# FYP_DevBoard.net
KiCad netlist of a schematic drawn in EasyEDA
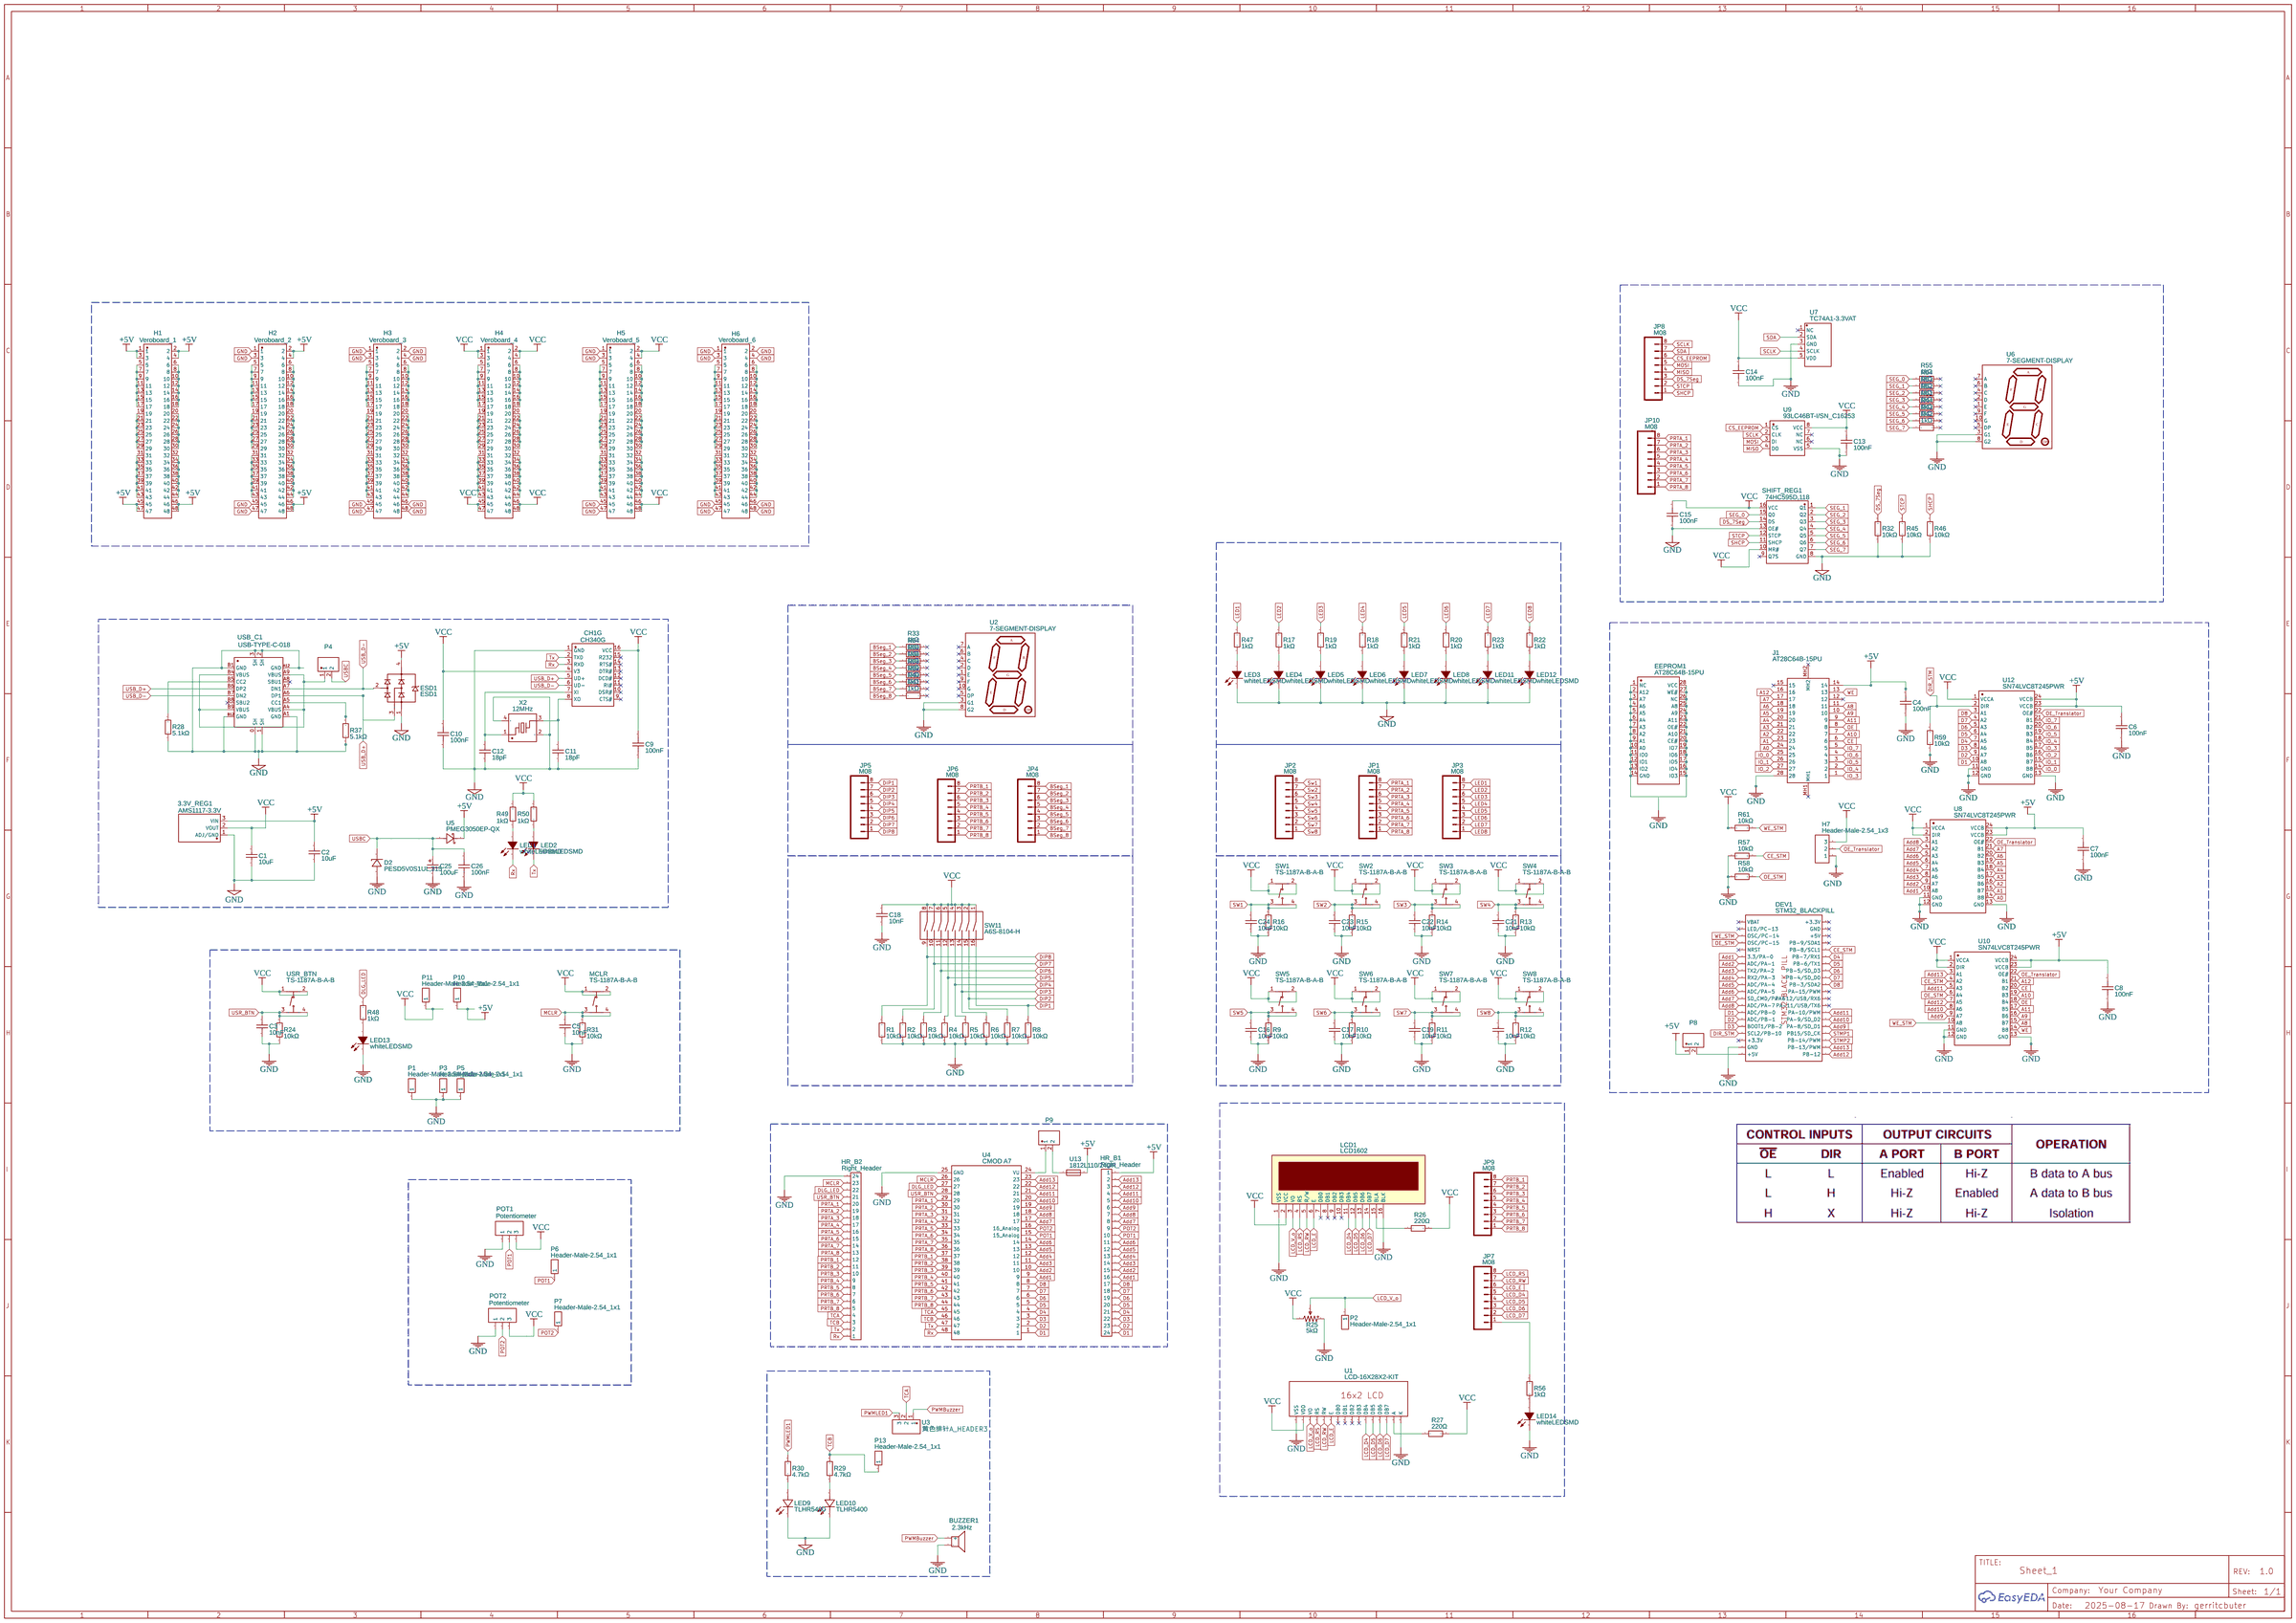
[diagram p0: schematic sheet]

(export (version "E")
  (design (tool "Eeschema 10.0.6"))
  (components
    (comp (ref "3.3V_REG1")
      (value "AMS1117-3.3V")
      (fields (field (name "Manufacturer") "MSKSEMI(美森科)"))
      (libsource (lib "") (part "AMS1117-3.3V_C5120796"))
    )
    (comp (ref "BUZZER1")
      (value "2.3kHz")
      (fields (field (name "Manufacturer") "华能"))
      (libsource (lib "") (part "TMB12A05"))
    )
    (comp (ref "C1")
      (value "10uF")
      (fields (field (name "Manufacturer") "SAMSUNG(三星)"))
      (libsource (lib "") (part "CL10A105KB8NNNC"))
    )
    (comp (ref "C2")
      (value "10uF")
      (fields (field (name "Manufacturer") "SAMSUNG(三星)"))
      (libsource (lib "") (part "CL10A105KB8NNNC"))
    )
    (comp (ref "C3")
      (value "10nF")
      (fields (field (name "Manufacturer Part") "0603B103K500NT") (field (name "Manufacturer") "FH(风华)"))
      (libsource (lib "") (part "0603B103K500NT"))
    )
    (comp (ref "C4")
      (value "100nF")
      (fields
        (field (name "Manufacturer Part") "CC0603KRX7R9BB104")
        (field (name "Manufacturer") "YAGEO(国巨)")
      )
      (libsource (lib "") (part "CC0603KRX7R9BB104"))
    )
    (comp (ref "C5")
      (value "10nF")
      (fields (field (name "Manufacturer Part") "0603B103K500NT") (field (name "Manufacturer") "FH(风华)"))
      (libsource (lib "") (part "0603B103K500NT"))
    )
    (comp (ref "C6")
      (value "100nF")
      (fields
        (field (name "Manufacturer Part") "CC0603KRX7R9BB104")
        (field (name "Manufacturer") "YAGEO(国巨)")
      )
      (libsource (lib "") (part "CC0603KRX7R9BB104"))
    )
    (comp (ref "C7")
      (value "100nF")
      (fields
        (field (name "Manufacturer Part") "CC0603KRX7R9BB104")
        (field (name "Manufacturer") "YAGEO(国巨)")
      )
      (libsource (lib "") (part "CC0603KRX7R9BB104"))
    )
    (comp (ref "C8")
      (value "100nF")
      (fields
        (field (name "Manufacturer Part") "CC0603KRX7R9BB104")
        (field (name "Manufacturer") "YAGEO(国巨)")
      )
      (libsource (lib "") (part "CC0603KRX7R9BB104"))
    )
    (comp (ref "C9")
      (value "100nF")
      (fields
        (field (name "Manufacturer Part") "CC0603KRX7R9BB104")
        (field (name "Manufacturer") "YAGEO(国巨)")
      )
      (libsource (lib "") (part "CC0603KRX7R9BB104"))
    )
    (comp (ref "C10")
      (value "100nF")
      (fields
        (field (name "Manufacturer Part") "CC0603KRX7R9BB104")
        (field (name "Manufacturer") "YAGEO(国巨)")
      )
      (libsource (lib "") (part "CC0603KRX7R9BB104"))
    )
    (comp (ref "C11")
      (value "18pF")
      (fields
        (field (name "Manufacturer Part") "CL10C180JB8NNNC")
        (field (name "Manufacturer") "SAMSUNG(三星)")
      )
      (libsource (lib "") (part "CL10C180JB8NNNC"))
    )
    (comp (ref "C12")
      (value "18pF")
      (fields
        (field (name "Manufacturer Part") "CL10C180JB8NNNC")
        (field (name "Manufacturer") "SAMSUNG(三星)")
      )
      (libsource (lib "") (part "CL10C180JB8NNNC"))
    )
    (comp (ref "C13")
      (value "100nF")
      (fields
        (field (name "Manufacturer Part") "CC0603KRX7R9BB104")
        (field (name "Manufacturer") "YAGEO(国巨)")
      )
      (libsource (lib "") (part "CC0603KRX7R9BB104"))
    )
    (comp (ref "C14")
      (value "100nF")
      (fields
        (field (name "Manufacturer Part") "CC0603KRX7R9BB104")
        (field (name "Manufacturer") "YAGEO(国巨)")
      )
      (libsource (lib "") (part "CC0603KRX7R9BB104"))
    )
    (comp (ref "C15")
      (value "100nF")
      (fields
        (field (name "Manufacturer Part") "CC0603KRX7R9BB104")
        (field (name "Manufacturer") "YAGEO(国巨)")
      )
      (libsource (lib "") (part "CC0603KRX7R9BB104"))
    )
    (comp (ref "C16")
      (value "10nF")
      (fields (field (name "Manufacturer Part") "0603B103K500NT") (field (name "Manufacturer") "FH(风华)"))
      (libsource (lib "") (part "0603B103K500NT"))
    )
    (comp (ref "C17")
      (value "10nF")
      (fields (field (name "Manufacturer Part") "0603B103K500NT") (field (name "Manufacturer") "FH(风华)"))
      (libsource (lib "") (part "0603B103K500NT"))
    )
    (comp (ref "C18")
      (value "10nF")
      (fields (field (name "Manufacturer Part") "0603B103K500NT") (field (name "Manufacturer") "FH(风华)"))
      (libsource (lib "") (part "0603B103K500NT"))
    )
    (comp (ref "C19")
      (value "10nF")
      (fields (field (name "Manufacturer Part") "0603B103K500NT") (field (name "Manufacturer") "FH(风华)"))
      (libsource (lib "") (part "0603B103K500NT"))
    )
    (comp (ref "C20")
      (value "10nF")
      (fields (field (name "Manufacturer Part") "0603B103K500NT") (field (name "Manufacturer") "FH(风华)"))
      (libsource (lib "") (part "0603B103K500NT"))
    )
    (comp (ref "C21")
      (value "10nF")
      (fields (field (name "Manufacturer Part") "0603B103K500NT") (field (name "Manufacturer") "FH(风华)"))
      (libsource (lib "") (part "0603B103K500NT"))
    )
    (comp (ref "C22")
      (value "10nF")
      (fields (field (name "Manufacturer Part") "0603B103K500NT") (field (name "Manufacturer") "FH(风华)"))
      (libsource (lib "") (part "0603B103K500NT"))
    )
    (comp (ref "C23")
      (value "10nF")
      (fields (field (name "Manufacturer Part") "0603B103K500NT") (field (name "Manufacturer") "FH(风华)"))
      (libsource (lib "") (part "0603B103K500NT"))
    )
    (comp (ref "C24")
      (value "10nF")
      (fields (field (name "Manufacturer Part") "0603B103K500NT") (field (name "Manufacturer") "FH(风华)"))
      (libsource (lib "") (part "0603B103K500NT"))
    )
    (comp (ref "C25")
      (value "100uF")
      (fields (field (name "Manufacturer Part") "TAJB107K006RNJ") (field (name "Manufacturer") "Kyocera AVX"))
      (libsource (lib "") (part "TAJB107K006RNJ"))
    )
    (comp (ref "C26")
      (value "100nF")
      (fields
        (field (name "Manufacturer Part") "CC0603KRX7R9BB104")
        (field (name "Manufacturer") "YAGEO(国巨)")
      )
      (libsource (lib "") (part "CC0603KRX7R9BB104"))
    )
    (comp (ref "CH1G")
      (value "CH340G")
      (fields (field (name "Manufacturer") "WCH(南京沁恒)"))
      (libsource (lib "") (part "CH340G"))
    )
    (comp (ref "D2")
      (value "PESD5V0S1UL,315")
      (fields (field (name "Manufacturer") "Nexperia(安世)"))
      (libsource (lib "") (part "PESD5V0S1UL,315"))
    )
    (comp (ref "DEV1") (value "STM32_BLACKPILL") (libsource (lib "") (part "STM32_BLACKPILL")))
    (comp (ref "EEPROM1")
      (value "AT28C64B-15PU")
      (fields (field (name "Manufacturer") "MICROCHIP(美国微芯)"))
      (libsource (lib "") (part "AT28C64B-15PU"))
    )
    (comp (ref "ESD1")
      (value "ESD1")
      (fields
        (field (name "Manufacturer Part") "TPPRTR5V0U2X")
        (field (name "Manufacturer") "TECH PUBLIC(台舟)")
      )
      (libsource (lib "") (part "TPPRTR5V0U2X"))
    )
    (comp (ref "H1")
      (value "Veroboard_1")
      (fields (field (name "Manufacturer") "XKB Connectivity(中国星坤)"))
      (libsource (lib "") (part "X5521FV-2X24-C70D30-1000"))
    )
    (comp (ref "H2")
      (value "Veroboard_2")
      (fields (field (name "Manufacturer") "XKB Connectivity(中国星坤)"))
      (libsource (lib "") (part "X5521FV-2X24-C70D30-1000"))
    )
    (comp (ref "H3")
      (value "Veroboard_3")
      (fields (field (name "Manufacturer") "XKB Connectivity(中国星坤)"))
      (libsource (lib "") (part "X5521FV-2X24-C70D30-1000"))
    )
    (comp (ref "H4")
      (value "Veroboard_4")
      (fields (field (name "Manufacturer") "XKB Connectivity(中国星坤)"))
      (libsource (lib "") (part "X5521FV-2X24-C70D30-1000"))
    )
    (comp (ref "H5")
      (value "Veroboard_5")
      (fields (field (name "Manufacturer") "XKB Connectivity(中国星坤)"))
      (libsource (lib "") (part "X5521FV-2X24-C70D30-1000"))
    )
    (comp (ref "H6")
      (value "Veroboard_6")
      (fields (field (name "Manufacturer") "XKB Connectivity(中国星坤)"))
      (libsource (lib "") (part "X5521FV-2X24-C70D30-1000"))
    )
    (comp (ref "H7")
      (value "Header-Male-2.54_1x3")
      (fields (field (name "Manufacturer Part") "2.54-1*3P针") (field (name "Manufacturer") "BOOMELE(博穆精密)"))
      (libsource (lib "") (part "Header-Male-2.54_1x3"))
    )
    (comp (ref "HR_B1") (value "Right_Header") (libsource (lib "") (part "Header_Female_2.54_1x24")))
    (comp (ref "HR_B2") (value "Right_Header") (libsource (lib "") (part "Header_Female_2.54_1x24_1")))
    (comp (ref "J1") (value "AT28C64B-15PU") (libsource (lib "") (part "28-6554-10")))
    (comp (ref "JP1") (value "M08") (libsource (lib "") (part "M08")))
    (comp (ref "JP2") (value "M08") (libsource (lib "") (part "M08")))
    (comp (ref "JP3") (value "M08") (libsource (lib "") (part "M08")))
    (comp (ref "JP4") (value "M08") (libsource (lib "") (part "M08")))
    (comp (ref "JP5") (value "M08") (libsource (lib "") (part "M08")))
    (comp (ref "JP6") (value "M08") (libsource (lib "") (part "M08")))
    (comp (ref "JP7") (value "M08") (libsource (lib "") (part "M08")))
    (comp (ref "JP8") (value "M08") (libsource (lib "") (part "M08")))
    (comp (ref "JP9") (value "M08") (libsource (lib "") (part "M08")))
    (comp (ref "JP10") (value "M08") (libsource (lib "") (part "M08")))
    (comp (ref "LCD1")
      (value "LCD1602")
      (fields
        (field (name "Manufacturer Part") "LCM1602K-NSW-BBW")
        (field (name "Manufacturer") "LONTECH(厦门龙特)")
      )
      (libsource (lib "") (part "LCD1602"))
    )
    (comp (ref "LED1")
      (value "whiteLEDSMD")
      (fields (field (name "Manufacturer Part") "KT-0805W") (field (name "Manufacturer") "KENTO"))
      (libsource (lib "") (part "whiteLEDSMD"))
    )
    (comp (ref "LED2")
      (value "whiteLEDSMD")
      (fields (field (name "Manufacturer Part") "KT-0805W") (field (name "Manufacturer") "KENTO"))
      (libsource (lib "") (part "whiteLEDSMD"))
    )
    (comp (ref "LED3")
      (value "whiteLEDSMD")
      (fields (field (name "Manufacturer Part") "KT-0805W") (field (name "Manufacturer") "KENTO"))
      (libsource (lib "") (part "whiteLEDSMD"))
    )
    (comp (ref "LED4")
      (value "whiteLEDSMD")
      (fields (field (name "Manufacturer Part") "KT-0805W") (field (name "Manufacturer") "KENTO"))
      (libsource (lib "") (part "whiteLEDSMD"))
    )
    (comp (ref "LED5")
      (value "whiteLEDSMD")
      (fields (field (name "Manufacturer Part") "KT-0805W") (field (name "Manufacturer") "KENTO"))
      (libsource (lib "") (part "whiteLEDSMD"))
    )
    (comp (ref "LED6")
      (value "whiteLEDSMD")
      (fields (field (name "Manufacturer Part") "KT-0805W") (field (name "Manufacturer") "KENTO"))
      (libsource (lib "") (part "whiteLEDSMD"))
    )
    (comp (ref "LED7")
      (value "whiteLEDSMD")
      (fields (field (name "Manufacturer Part") "KT-0805W") (field (name "Manufacturer") "KENTO"))
      (libsource (lib "") (part "whiteLEDSMD"))
    )
    (comp (ref "LED8")
      (value "whiteLEDSMD")
      (fields (field (name "Manufacturer Part") "KT-0805W") (field (name "Manufacturer") "KENTO"))
      (libsource (lib "") (part "whiteLEDSMD"))
    )
    (comp (ref "LED9")
      (value "TLHR5400")
      (fields (field (name "Manufacturer") "VISHAY(威世)"))
      (libsource (lib "") (part "TLHR5400"))
    )
    (comp (ref "LED10")
      (value "TLHR5400")
      (fields (field (name "Manufacturer") "VISHAY(威世)"))
      (libsource (lib "") (part "TLHR5400"))
    )
    (comp (ref "LED11")
      (value "whiteLEDSMD")
      (fields (field (name "Manufacturer Part") "KT-0805W") (field (name "Manufacturer") "KENTO"))
      (libsource (lib "") (part "whiteLEDSMD"))
    )
    (comp (ref "LED12")
      (value "whiteLEDSMD")
      (fields (field (name "Manufacturer Part") "KT-0805W") (field (name "Manufacturer") "KENTO"))
      (libsource (lib "") (part "whiteLEDSMD"))
    )
    (comp (ref "LED13")
      (value "whiteLEDSMD")
      (fields (field (name "Manufacturer Part") "KT-0805W") (field (name "Manufacturer") "KENTO"))
      (libsource (lib "") (part "whiteLEDSMD"))
    )
    (comp (ref "LED14")
      (value "whiteLEDSMD")
      (fields (field (name "Manufacturer Part") "KT-0805W") (field (name "Manufacturer") "KENTO"))
      (libsource (lib "") (part "whiteLEDSMD"))
    )
    (comp (ref "MCLR")
      (value "TS-1187A-B-A-B")
      (fields (field (name "Manufacturer") "XKB Connection(中国星坤)"))
      (libsource (lib "") (part "TS-1187A-B-A-B_1"))
    )
    (comp (ref "P1")
      (value "Header-Male-2.54_1x1")
      (fields (field (name "Manufacturer") "BOOMELE(博穆精密)"))
      (libsource (lib "") (part "Header-Male-2.54_1x1"))
    )
    (comp (ref "P2")
      (value "Header-Male-2.54_1x1")
      (fields (field (name "Manufacturer") "BOOMELE(博穆精密)"))
      (libsource (lib "") (part "Header-Male-2.54_1x1_1"))
    )
    (comp (ref "P3")
      (value "Header-Male-2.54_1x1")
      (fields (field (name "Manufacturer") "BOOMELE(博穆精密)"))
      (libsource (lib "") (part "Header-Male-2.54_1x1"))
    )
    (comp (ref "P4")
      (value "Female header1*2P")
      (fields (field (name "Manufacturer Part") "2.0-1*2P母") (field (name "Manufacturer") "BOOMELE(博穆精密)"))
      (libsource (lib "") (part "Female header1*2P"))
    )
    (comp (ref "P5")
      (value "Header-Male-2.54_1x1")
      (fields (field (name "Manufacturer") "BOOMELE(博穆精密)"))
      (libsource (lib "") (part "Header-Male-2.54_1x1"))
    )
    (comp (ref "P6")
      (value "Header-Male-2.54_1x1")
      (fields (field (name "Manufacturer") "BOOMELE(博穆精密)"))
      (libsource (lib "") (part "Header-Male-2.54_1x1"))
    )
    (comp (ref "P7")
      (value "Header-Male-2.54_1x1")
      (fields (field (name "Manufacturer") "BOOMELE(博穆精密)"))
      (libsource (lib "") (part "Header-Male-2.54_1x1"))
    )
    (comp (ref "P8")
      (value "Female header1*2P")
      (fields (field (name "Manufacturer Part") "2.0-1*2P母") (field (name "Manufacturer") "BOOMELE(博穆精密)"))
      (libsource (lib "") (part "Female header1*2P"))
    )
    (comp (ref "P9")
      (value "Female header1*2P")
      (fields (field (name "Manufacturer Part") "2.0-1*2P母") (field (name "Manufacturer") "BOOMELE(博穆精密)"))
      (libsource (lib "") (part "Female header1*2P"))
    )
    (comp (ref "P10")
      (value "Header-Male-2.54_1x1")
      (fields (field (name "Manufacturer") "BOOMELE(博穆精密)"))
      (libsource (lib "") (part "Header-Male-2.54_1x1"))
    )
    (comp (ref "P11")
      (value "Header-Male-2.54_1x1")
      (fields (field (name "Manufacturer") "BOOMELE(博穆精密)"))
      (libsource (lib "") (part "Header-Male-2.54_1x1"))
    )
    (comp (ref "P13")
      (value "Header-Male-2.54_1x1")
      (fields (field (name "Manufacturer") "BOOMELE(博穆精密)"))
      (libsource (lib "") (part "Header-Male-2.54_1x1"))
    )
    (comp (ref "POT1") (value "Potentiometer") (libsource (lib "") (part "Header-Male-2.54_1x3_1")))
    (comp (ref "POT2") (value "Potentiometer") (libsource (lib "") (part "Header-Male-2.54_1x3_1")))
    (comp (ref "R1")
      (value "10kΩ")
      (fields
        (field (name "Manufacturer Part") "0603WAF1002T5E")
        (field (name "Manufacturer") "UNI-ROYAL(厚声)")
      )
      (libsource (lib "") (part "0603WAF1002T5E"))
    )
    (comp (ref "R2")
      (value "10kΩ")
      (fields
        (field (name "Manufacturer Part") "0603WAF1002T5E")
        (field (name "Manufacturer") "UNI-ROYAL(厚声)")
      )
      (libsource (lib "") (part "0603WAF1002T5E"))
    )
    (comp (ref "R3")
      (value "10kΩ")
      (fields
        (field (name "Manufacturer Part") "0603WAF1002T5E")
        (field (name "Manufacturer") "UNI-ROYAL(厚声)")
      )
      (libsource (lib "") (part "0603WAF1002T5E"))
    )
    (comp (ref "R4")
      (value "10kΩ")
      (fields
        (field (name "Manufacturer Part") "0603WAF1002T5E")
        (field (name "Manufacturer") "UNI-ROYAL(厚声)")
      )
      (libsource (lib "") (part "0603WAF1002T5E"))
    )
    (comp (ref "R5")
      (value "10kΩ")
      (fields
        (field (name "Manufacturer Part") "0603WAF1002T5E")
        (field (name "Manufacturer") "UNI-ROYAL(厚声)")
      )
      (libsource (lib "") (part "0603WAF1002T5E"))
    )
    (comp (ref "R6")
      (value "10kΩ")
      (fields
        (field (name "Manufacturer Part") "0603WAF1002T5E")
        (field (name "Manufacturer") "UNI-ROYAL(厚声)")
      )
      (libsource (lib "") (part "0603WAF1002T5E"))
    )
    (comp (ref "R7")
      (value "10kΩ")
      (fields
        (field (name "Manufacturer Part") "0603WAF1002T5E")
        (field (name "Manufacturer") "UNI-ROYAL(厚声)")
      )
      (libsource (lib "") (part "0603WAF1002T5E"))
    )
    (comp (ref "R8")
      (value "10kΩ")
      (fields
        (field (name "Manufacturer Part") "0603WAF1002T5E")
        (field (name "Manufacturer") "UNI-ROYAL(厚声)")
      )
      (libsource (lib "") (part "0603WAF1002T5E"))
    )
    (comp (ref "R9")
      (value "10kΩ")
      (fields
        (field (name "Manufacturer Part") "0603WAF1002T5E")
        (field (name "Manufacturer") "UNI-ROYAL(厚声)")
      )
      (libsource (lib "") (part "0603WAF1002T5E"))
    )
    (comp (ref "R10")
      (value "10kΩ")
      (fields
        (field (name "Manufacturer Part") "0603WAF1002T5E")
        (field (name "Manufacturer") "UNI-ROYAL(厚声)")
      )
      (libsource (lib "") (part "0603WAF1002T5E"))
    )
    (comp (ref "R11")
      (value "10kΩ")
      (fields
        (field (name "Manufacturer Part") "0603WAF1002T5E")
        (field (name "Manufacturer") "UNI-ROYAL(厚声)")
      )
      (libsource (lib "") (part "0603WAF1002T5E"))
    )
    (comp (ref "R12")
      (value "10kΩ")
      (fields
        (field (name "Manufacturer Part") "0603WAF1002T5E")
        (field (name "Manufacturer") "UNI-ROYAL(厚声)")
      )
      (libsource (lib "") (part "0603WAF1002T5E"))
    )
    (comp (ref "R13")
      (value "10kΩ")
      (fields
        (field (name "Manufacturer Part") "0603WAF1002T5E")
        (field (name "Manufacturer") "UNI-ROYAL(厚声)")
      )
      (libsource (lib "") (part "0603WAF1002T5E"))
    )
    (comp (ref "R14")
      (value "10kΩ")
      (fields
        (field (name "Manufacturer Part") "0603WAF1002T5E")
        (field (name "Manufacturer") "UNI-ROYAL(厚声)")
      )
      (libsource (lib "") (part "0603WAF1002T5E"))
    )
    (comp (ref "R15")
      (value "10kΩ")
      (fields
        (field (name "Manufacturer Part") "0603WAF1002T5E")
        (field (name "Manufacturer") "UNI-ROYAL(厚声)")
      )
      (libsource (lib "") (part "0603WAF1002T5E"))
    )
    (comp (ref "R16")
      (value "10kΩ")
      (fields
        (field (name "Manufacturer Part") "0603WAF1002T5E")
        (field (name "Manufacturer") "UNI-ROYAL(厚声)")
      )
      (libsource (lib "") (part "0603WAF1002T5E"))
    )
    (comp (ref "R17")
      (value "1kΩ")
      (fields
        (field (name "Manufacturer Part") "0402WGF1001TCE")
        (field (name "Manufacturer") "UNI-ROYAL(厚声)")
      )
      (libsource (lib "") (part "0402WGF1001TCE"))
    )
    (comp (ref "R18")
      (value "1kΩ")
      (fields
        (field (name "Manufacturer Part") "0402WGF1001TCE")
        (field (name "Manufacturer") "UNI-ROYAL(厚声)")
      )
      (libsource (lib "") (part "0402WGF1001TCE"))
    )
    (comp (ref "R19")
      (value "1kΩ")
      (fields
        (field (name "Manufacturer Part") "0402WGF1001TCE")
        (field (name "Manufacturer") "UNI-ROYAL(厚声)")
      )
      (libsource (lib "") (part "0402WGF1001TCE"))
    )
    (comp (ref "R20")
      (value "1kΩ")
      (fields
        (field (name "Manufacturer Part") "0402WGF1001TCE")
        (field (name "Manufacturer") "UNI-ROYAL(厚声)")
      )
      (libsource (lib "") (part "0402WGF1001TCE"))
    )
    (comp (ref "R21")
      (value "1kΩ")
      (fields
        (field (name "Manufacturer Part") "0402WGF1001TCE")
        (field (name "Manufacturer") "UNI-ROYAL(厚声)")
      )
      (libsource (lib "") (part "0402WGF1001TCE"))
    )
    (comp (ref "R22")
      (value "1kΩ")
      (fields
        (field (name "Manufacturer Part") "0402WGF1001TCE")
        (field (name "Manufacturer") "UNI-ROYAL(厚声)")
      )
      (libsource (lib "") (part "0402WGF1001TCE"))
    )
    (comp (ref "R23")
      (value "1kΩ")
      (fields
        (field (name "Manufacturer Part") "0402WGF1001TCE")
        (field (name "Manufacturer") "UNI-ROYAL(厚声)")
      )
      (libsource (lib "") (part "0402WGF1001TCE"))
    )
    (comp (ref "R24")
      (value "10kΩ")
      (fields
        (field (name "Manufacturer Part") "0603WAF1002T5E")
        (field (name "Manufacturer") "UNI-ROYAL(厚声)")
      )
      (libsource (lib "") (part "0603WAF1002T5E"))
    )
    (comp (ref "R25")
      (value "5kΩ")
      (fields (field (name "Manufacturer Part") "3296Y-1-502LF") (field (name "Manufacturer") "BOURNS"))
      (libsource (lib "") (part "3296Y-1-502LF"))
    )
    (comp (ref "R26")
      (value "220Ω")
      (fields
        (field (name "Manufacturer Part") "0603WAF2200T5E")
        (field (name "Manufacturer") "UNI-ROYAL(厚声)")
      )
      (libsource (lib "") (part "0603WAF2200T5E"))
    )
    (comp (ref "R27")
      (value "220Ω")
      (fields
        (field (name "Manufacturer Part") "0603WAF2200T5E")
        (field (name "Manufacturer") "UNI-ROYAL(厚声)")
      )
      (libsource (lib "") (part "0603WAF2200T5E"))
    )
    (comp (ref "R28")
      (value "5.1kΩ")
      (fields
        (field (name "Manufacturer Part") "0603WAF5101T5E")
        (field (name "Manufacturer") "UNI-ROYAL(厚声)")
      )
      (libsource (lib "") (part "0603WAF5101T5E"))
    )
    (comp (ref "R29")
      (value "4.7kΩ")
      (fields
        (field (name "Manufacturer Part") "0402WGF4701TCE")
        (field (name "Manufacturer") "UNI-ROYAL(厚声)")
      )
      (libsource (lib "") (part "0402WGF4701TCE"))
    )
    (comp (ref "R30")
      (value "4.7kΩ")
      (fields
        (field (name "Manufacturer Part") "0402WGF4701TCE")
        (field (name "Manufacturer") "UNI-ROYAL(厚声)")
      )
      (libsource (lib "") (part "0402WGF4701TCE"))
    )
    (comp (ref "R31")
      (value "10kΩ")
      (fields
        (field (name "Manufacturer Part") "0603WAF1002T5E")
        (field (name "Manufacturer") "UNI-ROYAL(厚声)")
      )
      (libsource (lib "") (part "0603WAF1002T5E"))
    )
    (comp (ref "R32")
      (value "10kΩ")
      (fields
        (field (name "Manufacturer Part") "0603WAF1002T5E")
        (field (name "Manufacturer") "UNI-ROYAL(厚声)")
      )
      (libsource (lib "") (part "0603WAF1002T5E"))
    )
    (comp (ref "R33")
      (value "1kΩ")
      (fields (field (name "Manufacturer") "UNI-ROYAL(厚声)"))
      (libsource (lib "") (part "0603WAF1001T5E_2"))
    )
    (comp (ref "R34")
      (value "1kΩ")
      (fields (field (name "Manufacturer") "UNI-ROYAL(厚声)"))
      (libsource (lib "") (part "0603WAF1001T5E_2"))
    )
    (comp (ref "R35")
      (value "1kΩ")
      (fields (field (name "Manufacturer") "UNI-ROYAL(厚声)"))
      (libsource (lib "") (part "0603WAF1001T5E_2"))
    )
    (comp (ref "R36")
      (value "1kΩ")
      (fields (field (name "Manufacturer") "UNI-ROYAL(厚声)"))
      (libsource (lib "") (part "0603WAF1001T5E_2"))
    )
    (comp (ref "R37")
      (value "5.1kΩ")
      (fields
        (field (name "Manufacturer Part") "0603WAF5101T5E")
        (field (name "Manufacturer") "UNI-ROYAL(厚声)")
      )
      (libsource (lib "") (part "0603WAF5101T5E"))
    )
    (comp (ref "R38")
      (value "1kΩ")
      (fields (field (name "Manufacturer") "UNI-ROYAL(厚声)"))
      (libsource (lib "") (part "0603WAF1001T5E_2"))
    )
    (comp (ref "R39")
      (value "1kΩ")
      (fields (field (name "Manufacturer") "UNI-ROYAL(厚声)"))
      (libsource (lib "") (part "0603WAF1001T5E_2"))
    )
    (comp (ref "R40")
      (value "1kΩ")
      (fields (field (name "Manufacturer") "UNI-ROYAL(厚声)"))
      (libsource (lib "") (part "0603WAF1001T5E_2"))
    )
    (comp (ref "R41")
      (value "1kΩ")
      (fields (field (name "Manufacturer") "UNI-ROYAL(厚声)"))
      (libsource (lib "") (part "0603WAF1001T5E_2"))
    )
    (comp (ref "R42")
      (value "1kΩ")
      (fields (field (name "Manufacturer") "UNI-ROYAL(厚声)"))
      (libsource (lib "") (part "0603WAF1001T5E_2"))
    )
    (comp (ref "R43")
      (value "1kΩ")
      (fields (field (name "Manufacturer") "UNI-ROYAL(厚声)"))
      (libsource (lib "") (part "0603WAF1001T5E_2"))
    )
    (comp (ref "R44")
      (value "1kΩ")
      (fields (field (name "Manufacturer") "UNI-ROYAL(厚声)"))
      (libsource (lib "") (part "0603WAF1001T5E_2"))
    )
    (comp (ref "R45")
      (value "10kΩ")
      (fields
        (field (name "Manufacturer Part") "0603WAF1002T5E")
        (field (name "Manufacturer") "UNI-ROYAL(厚声)")
      )
      (libsource (lib "") (part "0603WAF1002T5E"))
    )
    (comp (ref "R46")
      (value "10kΩ")
      (fields
        (field (name "Manufacturer Part") "0603WAF1002T5E")
        (field (name "Manufacturer") "UNI-ROYAL(厚声)")
      )
      (libsource (lib "") (part "0603WAF1002T5E"))
    )
    (comp (ref "R47")
      (value "1kΩ")
      (fields
        (field (name "Manufacturer Part") "0402WGF1001TCE")
        (field (name "Manufacturer") "UNI-ROYAL(厚声)")
      )
      (libsource (lib "") (part "0402WGF1001TCE"))
    )
    (comp (ref "R48")
      (value "1kΩ")
      (fields (field (name "Manufacturer") "UNI-ROYAL(厚声)"))
      (libsource (lib "") (part "0603WAF1001T5E_1"))
    )
    (comp (ref "R49")
      (value "1kΩ")
      (fields (field (name "Manufacturer") "UNI-ROYAL(厚声)"))
      (libsource (lib "") (part "0603WAF1001T5E"))
    )
    (comp (ref "R50")
      (value "1kΩ")
      (fields (field (name "Manufacturer") "UNI-ROYAL(厚声)"))
      (libsource (lib "") (part "0603WAF1001T5E"))
    )
    (comp (ref "R51")
      (value "1kΩ")
      (fields (field (name "Manufacturer") "UNI-ROYAL(厚声)"))
      (libsource (lib "") (part "0603WAF1001T5E_2"))
    )
    (comp (ref "R52")
      (value "1kΩ")
      (fields (field (name "Manufacturer") "UNI-ROYAL(厚声)"))
      (libsource (lib "") (part "0603WAF1001T5E_2"))
    )
    (comp (ref "R53")
      (value "1kΩ")
      (fields (field (name "Manufacturer") "UNI-ROYAL(厚声)"))
      (libsource (lib "") (part "0603WAF1001T5E_2"))
    )
    (comp (ref "R54")
      (value "1kΩ")
      (fields (field (name "Manufacturer") "UNI-ROYAL(厚声)"))
      (libsource (lib "") (part "0603WAF1001T5E_2"))
    )
    (comp (ref "R55")
      (value "1kΩ")
      (fields (field (name "Manufacturer") "UNI-ROYAL(厚声)"))
      (libsource (lib "") (part "0603WAF1001T5E_2"))
    )
    (comp (ref "R56")
      (value "1kΩ")
      (fields (field (name "Manufacturer") "UNI-ROYAL(厚声)"))
      (libsource (lib "") (part "0603WAF1001T5E_1"))
    )
    (comp (ref "R57")
      (value "10kΩ")
      (fields
        (field (name "Manufacturer Part") "0603WAF1002T5E")
        (field (name "Manufacturer") "UNI-ROYAL(厚声)")
      )
      (libsource (lib "") (part "0603WAF1002T5E_1"))
    )
    (comp (ref "R58")
      (value "10kΩ")
      (fields
        (field (name "Manufacturer Part") "0603WAF1002T5E")
        (field (name "Manufacturer") "UNI-ROYAL(厚声)")
      )
      (libsource (lib "") (part "0603WAF1002T5E_1"))
    )
    (comp (ref "R59")
      (value "10kΩ")
      (fields
        (field (name "Manufacturer Part") "0603WAF1002T5E")
        (field (name "Manufacturer") "UNI-ROYAL(厚声)")
      )
      (libsource (lib "") (part "0603WAF1002T5E"))
    )
    (comp (ref "R61")
      (value "10kΩ")
      (fields
        (field (name "Manufacturer Part") "0603WAF1002T5E")
        (field (name "Manufacturer") "UNI-ROYAL(厚声)")
      )
      (libsource (lib "") (part "0603WAF1002T5E_1"))
    )
    (comp (ref "SHIFT_REG1")
      (value "74HC595D,118")
      (fields (field (name "Manufacturer") "Nexperia(安世)"))
      (libsource (lib "") (part "74HC595D,118"))
    )
    (comp (ref "SW1")
      (value "TS-1187A-B-A-B")
      (fields (field (name "Manufacturer") "XKB Connection(中国星坤)"))
      (libsource (lib "") (part "TS-1187A-B-A-B"))
    )
    (comp (ref "SW2")
      (value "TS-1187A-B-A-B")
      (fields (field (name "Manufacturer") "XKB Connection(中国星坤)"))
      (libsource (lib "") (part "TS-1187A-B-A-B"))
    )
    (comp (ref "SW3")
      (value "TS-1187A-B-A-B")
      (fields (field (name "Manufacturer") "XKB Connection(中国星坤)"))
      (libsource (lib "") (part "TS-1187A-B-A-B"))
    )
    (comp (ref "SW4")
      (value "TS-1187A-B-A-B")
      (fields (field (name "Manufacturer") "XKB Connection(中国星坤)"))
      (libsource (lib "") (part "TS-1187A-B-A-B"))
    )
    (comp (ref "SW5")
      (value "TS-1187A-B-A-B")
      (fields (field (name "Manufacturer") "XKB Connection(中国星坤)"))
      (libsource (lib "") (part "TS-1187A-B-A-B"))
    )
    (comp (ref "SW6")
      (value "TS-1187A-B-A-B")
      (fields (field (name "Manufacturer") "XKB Connection(中国星坤)"))
      (libsource (lib "") (part "TS-1187A-B-A-B"))
    )
    (comp (ref "SW7")
      (value "TS-1187A-B-A-B")
      (fields (field (name "Manufacturer") "XKB Connection(中国星坤)"))
      (libsource (lib "") (part "TS-1187A-B-A-B"))
    )
    (comp (ref "SW8")
      (value "TS-1187A-B-A-B")
      (fields (field (name "Manufacturer") "XKB Connection(中国星坤)"))
      (libsource (lib "") (part "TS-1187A-B-A-B"))
    )
    (comp (ref "SW11")
      (value "A6S-8104-H")
      (fields (field (name "Manufacturer") "OMRON(欧姆龙)"))
      (libsource (lib "") (part "A6S-8104-H"))
    )
    (comp (ref "U1") (value "LCD-16X28X2-KIT") (libsource (lib "") (part "LCD-16X28X2-KIT")))
    (comp (ref "U2") (value "7-SEGMENT-DISPLAY") (libsource (lib "") (part "7-SEGMENT-DISPLAY")))
    (comp (ref "U3") (value "黄色排针A_HEADER3") (libsource (lib "") (part "黄色排针A_HEADER3")))
    (comp (ref "U4")
      (value "CMOD A7")
      (fields (field (name "Manufacturer Part") "410-328-35") (field (name "Manufacturer") "Digilent Inc."))
      (libsource (lib "") (part "CMOD A7"))
    )
    (comp (ref "U5")
      (value "PMEG3050EP-QX")
      (fields (field (name "Manufacturer") "Nexperia(安世)"))
      (libsource (lib "") (part "PMEG3050EP-QX"))
    )
    (comp (ref "U6") (value "7-SEGMENT-DISPLAY") (libsource (lib "") (part "7-SEGMENT-DISPLAY")))
    (comp (ref "U7")
      (value "TC74A1-3.3VAT")
      (fields (field (name "Manufacturer") "MICROCHIP(美国微芯)"))
      (libsource (lib "") (part "TC74A1-3.3VAT"))
    )
    (comp (ref "U8")
      (value "SN74LVC8T245PWR")
      (fields (field (name "Manufacturer") "TI(德州仪器)"))
      (libsource (lib "") (part "SN74LVC8T245PWR"))
    )
    (comp (ref "U9")
      (value "93LC46BT-I/SN_C16253")
      (fields
        (field (name "Manufacturer Part") "93LC46BT-I/SN")
        (field (name "Manufacturer") "MICROCHIP(美国微芯)")
      )
      (libsource (lib "") (part "93LC46BT-I/SN_C16253"))
    )
    (comp (ref "U10")
      (value "SN74LVC8T245PWR")
      (fields (field (name "Manufacturer") "TI(德州仪器)"))
      (libsource (lib "") (part "SN74LVC8T245PWR"))
    )
    (comp (ref "U12")
      (value "SN74LVC8T245PWR")
      (fields (field (name "Manufacturer") "TI(德州仪器)"))
      (libsource (lib "") (part "SN74LVC8T245PWR"))
    )
    (comp (ref "U13")
      (value "1812L110/24DR")
      (fields (field (name "Manufacturer") "Littelfuse(美国力特)"))
      (libsource (lib "") (part "1812L110/24DR"))
    )
    (comp (ref "USB_C1")
      (value "USB-TYPE-C-018")
      (fields (field (name "Manufacturer") "DEALON(德艺隆)"))
      (libsource (lib "") (part "USB-TYPE-C-018"))
    )
    (comp (ref "USR_BTN")
      (value "TS-1187A-B-A-B")
      (fields (field (name "Manufacturer") "XKB Connection(中国星坤)"))
      (libsource (lib "") (part "TS-1187A-B-A-B_2"))
    )
    (comp (ref "X2")
      (value "12MHz")
      (fields (field (name "Manufacturer") "HD(浩都频率)"))
      (libsource (lib "") (part "7B012000Q01"))
    )
  )
  (nets
    (net (code "1") (name "+5V") (class "Default")
      (node (ref "3.3V_REG1") (pin "3") (pinfunction "VIN_3") (pintype "unspecified"))
      (node (ref "C2") (pin "2") (pinfunction "2_2") (pintype "input"))
      (node (ref "C4") (pin "2") (pinfunction "2_2") (pintype "unspecified"))
      (node (ref "C6") (pin "2") (pinfunction "2_2") (pintype "unspecified"))
      (node (ref "C7") (pin "2") (pinfunction "2_2") (pintype "unspecified"))
      (node (ref "C8") (pin "2") (pinfunction "2_2") (pintype "unspecified"))
      (node (ref "ESD1") (pin "4") (pinfunction "4_4") (pintype "unspecified"))
      (node (ref "H1") (pin "1") (pinfunction "1_1") (pintype "unspecified"))
      (node (ref "H1") (pin "2") (pinfunction "2_2") (pintype "unspecified"))
      (node (ref "H1") (pin "3") (pinfunction "3_3") (pintype "unspecified"))
      (node (ref "H1") (pin "4") (pinfunction "4_4") (pintype "unspecified"))
      (node (ref "H1") (pin "45") (pinfunction "45_45") (pintype "unspecified"))
      (node (ref "H1") (pin "46") (pinfunction "46_46") (pintype "unspecified"))
      (node (ref "H1") (pin "47") (pinfunction "47_47") (pintype "unspecified"))
      (node (ref "H1") (pin "48") (pinfunction "48_48") (pintype "unspecified"))
      (node (ref "H2") (pin "2") (pinfunction "2_2") (pintype "unspecified"))
      (node (ref "H2") (pin "4") (pinfunction "4_4") (pintype "unspecified"))
      (node (ref "H2") (pin "46") (pinfunction "46_46") (pintype "unspecified"))
      (node (ref "H2") (pin "48") (pinfunction "48_48") (pintype "unspecified"))
      (node (ref "HR_B1") (pin "1") (pinfunction "1_1") (pintype "unspecified"))
      (node (ref "J1") (pin "14") (pinfunction "14_14") (pintype "bidirectional"))
      (node (ref "P10") (pin "1") (pinfunction "1_1") (pintype "input"))
      (node (ref "P8") (pin "1") (pinfunction "1_1") (pintype "unspecified"))
      (node (ref "U10") (pin "23") (pinfunction "VCCB_23") (pintype "unspecified"))
      (node (ref "U10") (pin "24") (pinfunction "VCCB_24") (pintype "unspecified"))
      (node (ref "U12") (pin "23") (pinfunction "VCCB_23") (pintype "unspecified"))
      (node (ref "U12") (pin "24") (pinfunction "VCCB_24") (pintype "unspecified"))
      (node (ref "U13") (pin "2") (pinfunction "2_2") (pintype "unspecified"))
      (node (ref "U5") (pin "1") (pinfunction "K_1") (pintype "unspecified"))
      (node (ref "U8") (pin "23") (pinfunction "VCCB_23") (pintype "unspecified"))
      (node (ref "U8") (pin "24") (pinfunction "VCCB_24") (pintype "unspecified"))
    )
    (net (code "2") (name "A0") (class "Default")
      (node (ref "J1") (pin "24") (pinfunction "24_24") (pintype "bidirectional"))
      (node (ref "U8") (pin "14") (pinfunction "B8_14") (pintype "unspecified"))
    )
    (net (code "3") (name "A1") (class "Default")
      (node (ref "J1") (pin "23") (pinfunction "23_23") (pintype "bidirectional"))
      (node (ref "U8") (pin "15") (pinfunction "B7_15") (pintype "unspecified"))
    )
    (net (code "4") (name "A2") (class "Default")
      (node (ref "J1") (pin "22") (pinfunction "22_22") (pintype "bidirectional"))
      (node (ref "U8") (pin "16") (pinfunction "B6_16") (pintype "unspecified"))
    )
    (net (code "5") (name "A3") (class "Default")
      (node (ref "J1") (pin "21") (pinfunction "21_21") (pintype "bidirectional"))
      (node (ref "U8") (pin "17") (pinfunction "B5_17") (pintype "unspecified"))
    )
    (net (code "6") (name "A4") (class "Default")
      (node (ref "J1") (pin "20") (pinfunction "20_20") (pintype "bidirectional"))
      (node (ref "U8") (pin "18") (pinfunction "B4_18") (pintype "unspecified"))
    )
    (net (code "7") (name "A5") (class "Default")
      (node (ref "J1") (pin "19") (pinfunction "19_19") (pintype "bidirectional"))
      (node (ref "U8") (pin "19") (pinfunction "B3_19") (pintype "unspecified"))
    )
    (net (code "8") (name "A6") (class "Default")
      (node (ref "J1") (pin "18") (pinfunction "18_18") (pintype "bidirectional"))
      (node (ref "U8") (pin "20") (pinfunction "B2_20") (pintype "unspecified"))
    )
    (net (code "9") (name "A7") (class "Default")
      (node (ref "J1") (pin "17") (pinfunction "17_17") (pintype "bidirectional"))
      (node (ref "U8") (pin "21") (pinfunction "B1_21") (pintype "unspecified"))
    )
    (net (code "10") (name "A8") (class "Default")
      (node (ref "J1") (pin "11") (pinfunction "11_11") (pintype "bidirectional"))
      (node (ref "U10") (pin "15") (pinfunction "B7_15") (pintype "unspecified"))
    )
    (net (code "11") (name "A9") (class "Default")
      (node (ref "J1") (pin "10") (pinfunction "10_10") (pintype "bidirectional"))
      (node (ref "U10") (pin "16") (pinfunction "B6_16") (pintype "unspecified"))
    )
    (net (code "12") (name "A10") (class "Default")
      (node (ref "J1") (pin "7") (pinfunction "7_7") (pintype "bidirectional"))
      (node (ref "U10") (pin "19") (pinfunction "B3_19") (pintype "unspecified"))
    )
    (net (code "13") (name "A11") (class "Default")
      (node (ref "J1") (pin "9") (pinfunction "9_9") (pintype "bidirectional"))
      (node (ref "U10") (pin "17") (pinfunction "B5_17") (pintype "unspecified"))
    )
    (net (code "14") (name "A12") (class "Default")
      (node (ref "J1") (pin "16") (pinfunction "16_16") (pintype "bidirectional"))
      (node (ref "U10") (pin "21") (pinfunction "B1_21") (pintype "unspecified"))
    )
    (net (code "15") (name "Add1") (class "Default")
      (node (ref "DEV1") (pin "26") (pinfunction "3.3/PA-0_26") (pintype "unspecified"))
      (node (ref "HR_B1") (pin "16") (pinfunction "16_16") (pintype "unspecified"))
      (node (ref "U4") (pin "9") (pinfunction "9_9") (pintype "unspecified"))
      (node (ref "U8") (pin "10") (pinfunction "A8_10") (pintype "unspecified"))
    )
    (net (code "16") (name "Add2") (class "Default")
      (node (ref "DEV1") (pin "27") (pinfunction "ADC/PA-1_27") (pintype "unspecified"))
      (node (ref "HR_B1") (pin "15") (pinfunction "15_15") (pintype "unspecified"))
      (node (ref "U4") (pin "10") (pinfunction "10_10") (pintype "unspecified"))
      (node (ref "U8") (pin "9") (pinfunction "A7_9") (pintype "unspecified"))
    )
    (net (code "17") (name "Add3") (class "Default")
      (node (ref "DEV1") (pin "28") (pinfunction "TX2/PA-2_28") (pintype "unspecified"))
      (node (ref "HR_B1") (pin "14") (pinfunction "14_14") (pintype "unspecified"))
      (node (ref "U4") (pin "11") (pinfunction "11_11") (pintype "unspecified"))
      (node (ref "U8") (pin "8") (pinfunction "A6_8") (pintype "unspecified"))
    )
    (net (code "18") (name "Add4") (class "Default")
      (node (ref "DEV1") (pin "29") (pinfunction "RX2/PA-3_29") (pintype "unspecified"))
      (node (ref "HR_B1") (pin "13") (pinfunction "13_13") (pintype "unspecified"))
      (node (ref "U4") (pin "12") (pinfunction "12_12") (pintype "unspecified"))
      (node (ref "U8") (pin "7") (pinfunction "A5_7") (pintype "unspecified"))
    )
    (net (code "19") (name "Add5") (class "Default")
      (node (ref "DEV1") (pin "30") (pinfunction "ADC/PA-4_30") (pintype "unspecified"))
      (node (ref "HR_B1") (pin "12") (pinfunction "12_12") (pintype "unspecified"))
      (node (ref "U4") (pin "13") (pinfunction "13_13") (pintype "unspecified"))
      (node (ref "U8") (pin "6") (pinfunction "A4_6") (pintype "unspecified"))
    )
    (net (code "20") (name "Add6") (class "Default")
      (node (ref "DEV1") (pin "31") (pinfunction "ADC/PA-5_31") (pintype "unspecified"))
      (node (ref "HR_B1") (pin "11") (pinfunction "11_11") (pintype "unspecified"))
      (node (ref "U4") (pin "14") (pinfunction "14_14") (pintype "unspecified"))
      (node (ref "U8") (pin "5") (pinfunction "A3_5") (pintype "unspecified"))
    )
    (net (code "21") (name "Add7") (class "Default")
      (node (ref "DEV1") (pin "32") (pinfunction "SD_CMD/PA-6_32") (pintype "unspecified"))
      (node (ref "HR_B1") (pin "8") (pinfunction "8_8") (pintype "unspecified"))
      (node (ref "U4") (pin "17") (pinfunction "17_17") (pintype "unspecified"))
      (node (ref "U8") (pin "4") (pinfunction "A2_4") (pintype "unspecified"))
    )
    (net (code "22") (name "Add8") (class "Default")
      (node (ref "DEV1") (pin "33") (pinfunction "ADC/PA-7_33") (pintype "unspecified"))
      (node (ref "HR_B1") (pin "7") (pinfunction "7_7") (pintype "unspecified"))
      (node (ref "U4") (pin "18") (pinfunction "18_18") (pintype "unspecified"))
      (node (ref "U8") (pin "3") (pinfunction "A1_3") (pintype "unspecified"))
    )
    (net (code "23") (name "Add9") (class "Default")
      (node (ref "DEV1") (pin "5") (pinfunction "PA-8/SD_D1_5") (pintype "unspecified"))
      (node (ref "HR_B1") (pin "6") (pinfunction "6_6") (pintype "unspecified"))
      (node (ref "U10") (pin "9") (pinfunction "A7_9") (pintype "unspecified"))
      (node (ref "U4") (pin "19") (pinfunction "19_19") (pintype "unspecified"))
    )
    (net (code "24") (name "Add10") (class "Default")
      (node (ref "DEV1") (pin "6") (pinfunction "PA-9/SD_D2_6") (pintype "unspecified"))
      (node (ref "HR_B1") (pin "5") (pinfunction "5_5") (pintype "unspecified"))
      (node (ref "U10") (pin "8") (pinfunction "A6_8") (pintype "unspecified"))
      (node (ref "U4") (pin "20") (pinfunction "20_20") (pintype "unspecified"))
    )
    (net (code "25") (name "Add11") (class "Default")
      (node (ref "DEV1") (pin "7") (pinfunction "PA-10/PWM_7") (pintype "unspecified"))
      (node (ref "HR_B1") (pin "4") (pinfunction "4_4") (pintype "unspecified"))
      (node (ref "U10") (pin "5") (pinfunction "A3_5") (pintype "unspecified"))
      (node (ref "U4") (pin "21") (pinfunction "21_21") (pintype "unspecified"))
    )
    (net (code "26") (name "Add12") (class "Default")
      (node (ref "DEV1") (pin "1") (pinfunction "PB-12_1") (pintype "unspecified"))
      (node (ref "HR_B1") (pin "3") (pinfunction "3_3") (pintype "unspecified"))
      (node (ref "U10") (pin "7") (pinfunction "A5_7") (pintype "unspecified"))
      (node (ref "U4") (pin "22") (pinfunction "22_22") (pintype "unspecified"))
    )
    (net (code "27") (name "Add13") (class "Default")
      (node (ref "DEV1") (pin "2") (pinfunction "PB-13/PWM_2") (pintype "unspecified"))
      (node (ref "HR_B1") (pin "2") (pinfunction "2_2") (pintype "unspecified"))
      (node (ref "U10") (pin "3") (pinfunction "A1_3") (pintype "unspecified"))
      (node (ref "U4") (pin "23") (pinfunction "23_23") (pintype "unspecified"))
    )
    (net (code "28") (name "BSeg_1") (class "Default")
      (node (ref "JP4") (pin "8") (pinfunction "8_8") (pintype "unspecified"))
      (node (ref "R33") (pin "1") (pinfunction "1_1") (pintype "input"))
    )
    (net (code "29") (name "BSeg_2") (class "Default")
      (node (ref "JP4") (pin "7") (pinfunction "7_7") (pintype "unspecified"))
      (node (ref "R34") (pin "1") (pinfunction "1_1") (pintype "input"))
    )
    (net (code "30") (name "BSeg_3") (class "Default")
      (node (ref "JP4") (pin "6") (pinfunction "6_6") (pintype "unspecified"))
      (node (ref "R35") (pin "1") (pinfunction "1_1") (pintype "input"))
    )
    (net (code "31") (name "BSeg_4") (class "Default")
      (node (ref "JP4") (pin "5") (pinfunction "5_5") (pintype "unspecified"))
      (node (ref "R36") (pin "1") (pinfunction "1_1") (pintype "input"))
    )
    (net (code "32") (name "BSeg_5") (class "Default")
      (node (ref "JP4") (pin "4") (pinfunction "4_4") (pintype "unspecified"))
      (node (ref "R38") (pin "1") (pinfunction "1_1") (pintype "input"))
    )
    (net (code "33") (name "BSeg_6") (class "Default")
      (node (ref "JP4") (pin "3") (pinfunction "3_3") (pintype "unspecified"))
      (node (ref "R39") (pin "1") (pinfunction "1_1") (pintype "input"))
    )
    (net (code "34") (name "BSeg_7") (class "Default")
      (node (ref "JP4") (pin "2") (pinfunction "2_2") (pintype "unspecified"))
      (node (ref "R40") (pin "1") (pinfunction "1_1") (pintype "input"))
    )
    (net (code "35") (name "BSeg_8") (class "Default")
      (node (ref "JP4") (pin "1") (pinfunction "1_1") (pintype "unspecified"))
      (node (ref "R41") (pin "1") (pinfunction "1_1") (pintype "input"))
    )
    (net (code "36") (name "CE") (class "Default")
      (node (ref "J1") (pin "6") (pinfunction "6_6") (pintype "bidirectional"))
      (node (ref "U10") (pin "20") (pinfunction "B2_20") (pintype "unspecified"))
    )
    (net (code "37") (name "CE_STM") (class "Default")
      (node (ref "DEV1") (pin "16") (pinfunction "PB-8/SCL1_16") (pintype "unspecified"))
      (node (ref "R57") (pin "2") (pinfunction "2_2") (pintype "input"))
      (node (ref "U10") (pin "4") (pinfunction "A2_4") (pintype "unspecified"))
    )
    (net (code "38") (name "CS_EEPROM") (class "Default")
      (node (ref "JP8") (pin "6") (pinfunction "6_6") (pintype "unspecified"))
      (node (ref "U9") (pin "1") (pinfunction "CS_1") (pintype "unspecified"))
    )
    (net (code "39") (name "D1") (class "Default")
      (node (ref "DEV1") (pin "34") (pinfunction "ADC/PB-0_34") (pintype "unspecified"))
      (node (ref "HR_B1") (pin "24") (pinfunction "24_24") (pintype "unspecified"))
      (node (ref "U12") (pin "10") (pinfunction "A8_10") (pintype "unspecified"))
      (node (ref "U4") (pin "1") (pinfunction "1_1") (pintype "unspecified"))
    )
    (net (code "40") (name "D2") (class "Default")
      (node (ref "DEV1") (pin "35") (pinfunction "ADC/PB-1_35") (pintype "unspecified"))
      (node (ref "HR_B1") (pin "23") (pinfunction "23_23") (pintype "unspecified"))
      (node (ref "U12") (pin "9") (pinfunction "A7_9") (pintype "unspecified"))
      (node (ref "U4") (pin "2") (pinfunction "2_2") (pintype "unspecified"))
    )
    (net (code "41") (name "D3") (class "Default")
      (node (ref "DEV1") (pin "36") (pinfunction "BOOT1/PB-2_36") (pintype "unspecified"))
      (node (ref "HR_B1") (pin "22") (pinfunction "22_22") (pintype "unspecified"))
      (node (ref "U12") (pin "8") (pinfunction "A6_8") (pintype "unspecified"))
      (node (ref "U4") (pin "3") (pinfunction "3_3") (pintype "unspecified"))
    )
    (net (code "42") (name "D4") (class "Default")
      (node (ref "DEV1") (pin "15") (pinfunction "PB-7/RX1_15") (pintype "unspecified"))
      (node (ref "HR_B1") (pin "21") (pinfunction "21_21") (pintype "unspecified"))
      (node (ref "U12") (pin "7") (pinfunction "A5_7") (pintype "unspecified"))
      (node (ref "U4") (pin "4") (pinfunction "4_4") (pintype "unspecified"))
    )
    (net (code "43") (name "D5") (class "Default")
      (node (ref "DEV1") (pin "14") (pinfunction "PB-6/TX1_14") (pintype "unspecified"))
      (node (ref "HR_B1") (pin "20") (pinfunction "20_20") (pintype "unspecified"))
      (node (ref "U12") (pin "6") (pinfunction "A4_6") (pintype "unspecified"))
      (node (ref "U4") (pin "5") (pinfunction "5_5") (pintype "unspecified"))
    )
    (net (code "44") (name "D6") (class "Default")
      (node (ref "DEV1") (pin "13") (pinfunction "PB-5/SD_D3_13") (pintype "unspecified"))
      (node (ref "HR_B1") (pin "19") (pinfunction "19_19") (pintype "unspecified"))
      (node (ref "U12") (pin "5") (pinfunction "A3_5") (pintype "unspecified"))
      (node (ref "U4") (pin "6") (pinfunction "6_6") (pintype "unspecified"))
    )
    (net (code "45") (name "D7") (class "Default")
      (node (ref "DEV1") (pin "12") (pinfunction "PB-4/SD_D0_12") (pintype "unspecified"))
      (node (ref "HR_B1") (pin "18") (pinfunction "18_18") (pintype "unspecified"))
      (node (ref "U12") (pin "4") (pinfunction "A2_4") (pintype "unspecified"))
      (node (ref "U4") (pin "7") (pinfunction "7_7") (pintype "unspecified"))
    )
    (net (code "46") (name "D8") (class "Default")
      (node (ref "DEV1") (pin "11") (pinfunction "PB-3/SDA2_11") (pintype "unspecified"))
      (node (ref "HR_B1") (pin "17") (pinfunction "17_17") (pintype "unspecified"))
      (node (ref "U12") (pin "3") (pinfunction "A1_3") (pintype "unspecified"))
      (node (ref "U4") (pin "8") (pinfunction "8_8") (pintype "unspecified"))
    )
    (net (code "47") (name "DIP1") (class "Default")
      (node (ref "JP5") (pin "8") (pinfunction "8_8") (pintype "unspecified"))
      (node (ref "R8") (pin "2") (pinfunction "2_2") (pintype "input"))
      (node (ref "SW11") (pin "16") (pinfunction "16_16") (pintype "unspecified"))
    )
    (net (code "48") (name "DIP2") (class "Default")
      (node (ref "JP5") (pin "7") (pinfunction "7_7") (pintype "unspecified"))
      (node (ref "R7") (pin "2") (pinfunction "2_2") (pintype "input"))
      (node (ref "SW11") (pin "15") (pinfunction "15_15") (pintype "unspecified"))
    )
    (net (code "49") (name "DIP3") (class "Default")
      (node (ref "JP5") (pin "6") (pinfunction "6_6") (pintype "unspecified"))
      (node (ref "R6") (pin "2") (pinfunction "2_2") (pintype "input"))
      (node (ref "SW11") (pin "14") (pinfunction "14_14") (pintype "unspecified"))
    )
    (net (code "50") (name "DIP4") (class "Default")
      (node (ref "JP5") (pin "5") (pinfunction "5_5") (pintype "unspecified"))
      (node (ref "R5") (pin "2") (pinfunction "2_2") (pintype "input"))
      (node (ref "SW11") (pin "13") (pinfunction "13_13") (pintype "unspecified"))
    )
    (net (code "51") (name "DIP5") (class "Default")
      (node (ref "JP5") (pin "4") (pinfunction "4_4") (pintype "unspecified"))
      (node (ref "R4") (pin "2") (pinfunction "2_2") (pintype "input"))
      (node (ref "SW11") (pin "12") (pinfunction "12_12") (pintype "unspecified"))
    )
    (net (code "52") (name "DIP6") (class "Default")
      (node (ref "JP5") (pin "3") (pinfunction "3_3") (pintype "unspecified"))
      (node (ref "R3") (pin "2") (pinfunction "2_2") (pintype "input"))
      (node (ref "SW11") (pin "11") (pinfunction "11_11") (pintype "unspecified"))
    )
    (net (code "53") (name "DIP7") (class "Default")
      (node (ref "JP5") (pin "2") (pinfunction "2_2") (pintype "unspecified"))
      (node (ref "R2") (pin "2") (pinfunction "2_2") (pintype "input"))
      (node (ref "SW11") (pin "10") (pinfunction "10_10") (pintype "unspecified"))
    )
    (net (code "54") (name "DIP8") (class "Default")
      (node (ref "JP5") (pin "1") (pinfunction "1_1") (pintype "unspecified"))
      (node (ref "R1") (pin "2") (pinfunction "2_2") (pintype "input"))
      (node (ref "SW11") (pin "9") (pinfunction "9_9") (pintype "unspecified"))
    )
    (net (code "55") (name "DIR_STM") (class "Default")
      (node (ref "DEV1") (pin "37") (pinfunction "SCL2/PB-10_37") (pintype "unspecified"))
      (node (ref "R59") (pin "2") (pinfunction "2_2") (pintype "input"))
      (node (ref "U12") (pin "2") (pinfunction "DIR_2") (pintype "unspecified"))
    )
    (net (code "56") (name "DLG_LED") (class "Default")
      (node (ref "HR_B2") (pin "22") (pinfunction "22_22") (pintype "unspecified"))
      (node (ref "R48") (pin "1") (pinfunction "1_1") (pintype "input"))
      (node (ref "U4") (pin "27") (pinfunction "27_27") (pintype "unspecified"))
    )
    (net (code "57") (name "DS_7Seg") (class "Default")
      (node (ref "JP8") (pin "3") (pinfunction "3_3") (pintype "unspecified"))
      (node (ref "R32") (pin "2") (pinfunction "2_2") (pintype "input"))
      (node (ref "SHIFT_REG1") (pin "14") (pinfunction "DS_14") (pintype "unspecified"))
    )
    (net (code "58") (name "GND") (class "Default")
      (node (ref "3.3V_REG1") (pin "1") (pinfunction "ADJ/GND_1") (pintype "unspecified"))
      (node (ref "BUZZER1") (pin "2") (pinfunction "2_2") (pintype "unspecified"))
      (node (ref "C1") (pin "1") (pinfunction "1_1") (pintype "input"))
      (node (ref "C10") (pin "1") (pinfunction "1_1") (pintype "unspecified"))
      (node (ref "C11") (pin "1") (pinfunction "1_1") (pintype "input"))
      (node (ref "C12") (pin "1") (pinfunction "1_1") (pintype "input"))
      (node (ref "C13") (pin "1") (pinfunction "1_1") (pintype "unspecified"))
      (node (ref "C14") (pin "1") (pinfunction "1_1") (pintype "unspecified"))
      (node (ref "C15") (pin "1") (pinfunction "1_1") (pintype "unspecified"))
      (node (ref "C16") (pin "1") (pinfunction "1_1") (pintype "input"))
      (node (ref "C17") (pin "1") (pinfunction "1_1") (pintype "input"))
      (node (ref "C18") (pin "1") (pinfunction "1_1") (pintype "input"))
      (node (ref "C19") (pin "1") (pinfunction "1_1") (pintype "input"))
      (node (ref "C2") (pin "1") (pinfunction "1_1") (pintype "input"))
      (node (ref "C20") (pin "1") (pinfunction "1_1") (pintype "input"))
      (node (ref "C21") (pin "1") (pinfunction "1_1") (pintype "input"))
      (node (ref "C22") (pin "1") (pinfunction "1_1") (pintype "input"))
      (node (ref "C23") (pin "1") (pinfunction "1_1") (pintype "input"))
      (node (ref "C24") (pin "1") (pinfunction "1_1") (pintype "input"))
      (node (ref "C25") (pin "2") (pinfunction "2_2") (pintype "input"))
      (node (ref "C26") (pin "1") (pinfunction "1_1") (pintype "unspecified"))
      (node (ref "C3") (pin "1") (pinfunction "1_1") (pintype "input"))
      (node (ref "C4") (pin "1") (pinfunction "1_1") (pintype "unspecified"))
      (node (ref "C5") (pin "1") (pinfunction "1_1") (pintype "input"))
      (node (ref "C6") (pin "1") (pinfunction "1_1") (pintype "unspecified"))
      (node (ref "C7") (pin "1") (pinfunction "1_1") (pintype "unspecified"))
      (node (ref "C8") (pin "1") (pinfunction "1_1") (pintype "unspecified"))
      (node (ref "C9") (pin "1") (pinfunction "1_1") (pintype "unspecified"))
      (node (ref "CH1G") (pin "1") (pinfunction "GND_1") (pintype "unspecified"))
      (node (ref "D2") (pin "2") (pinfunction "A_2") (pintype "unspecified"))
      (node (ref "DEV1") (pin "39") (pinfunction "GND_39") (pintype "unspecified"))
      (node (ref "ESD1") (pin "1") (pinfunction "1_1") (pintype "unspecified"))
      (node (ref "H2") (pin "1") (pinfunction "1_1") (pintype "unspecified"))
      (node (ref "H2") (pin "3") (pinfunction "3_3") (pintype "unspecified"))
      (node (ref "H2") (pin "45") (pinfunction "45_45") (pintype "unspecified"))
      (node (ref "H2") (pin "47") (pinfunction "47_47") (pintype "unspecified"))
      (node (ref "H3") (pin "1") (pinfunction "1_1") (pintype "unspecified"))
      (node (ref "H3") (pin "2") (pinfunction "2_2") (pintype "unspecified"))
      (node (ref "H3") (pin "3") (pinfunction "3_3") (pintype "unspecified"))
      (node (ref "H3") (pin "4") (pinfunction "4_4") (pintype "unspecified"))
      (node (ref "H3") (pin "45") (pinfunction "45_45") (pintype "unspecified"))
      (node (ref "H3") (pin "46") (pinfunction "46_46") (pintype "unspecified"))
      (node (ref "H3") (pin "47") (pinfunction "47_47") (pintype "unspecified"))
      (node (ref "H3") (pin "48") (pinfunction "48_48") (pintype "unspecified"))
      (node (ref "H5") (pin "1") (pinfunction "1_1") (pintype "unspecified"))
      (node (ref "H5") (pin "3") (pinfunction "3_3") (pintype "unspecified"))
      (node (ref "H5") (pin "45") (pinfunction "45_45") (pintype "unspecified"))
      (node (ref "H5") (pin "47") (pinfunction "47_47") (pintype "unspecified"))
      (node (ref "H6") (pin "1") (pinfunction "1_1") (pintype "unspecified"))
      (node (ref "H6") (pin "2") (pinfunction "2_2") (pintype "unspecified"))
      (node (ref "H6") (pin "3") (pinfunction "3_3") (pintype "unspecified"))
      (node (ref "H6") (pin "4") (pinfunction "4_4") (pintype "unspecified"))
      (node (ref "H6") (pin "45") (pinfunction "45_45") (pintype "unspecified"))
      (node (ref "H6") (pin "46") (pinfunction "46_46") (pintype "unspecified"))
      (node (ref "H6") (pin "47") (pinfunction "47_47") (pintype "unspecified"))
      (node (ref "H6") (pin "48") (pinfunction "48_48") (pintype "unspecified"))
      (node (ref "H7") (pin "1") (pinfunction "1_1") (pintype "input"))
      (node (ref "HR_B2") (pin "24") (pinfunction "24_24") (pintype "unspecified"))
      (node (ref "J1") (pin "28") (pinfunction "28_28") (pintype "bidirectional"))
      (node (ref "LCD1") (pin "1") (pinfunction "VSS_1") (pintype "unspecified"))
      (node (ref "LCD1") (pin "16") (pinfunction "BLK_16") (pintype "unspecified"))
      (node (ref "LED10") (pin "1") (pinfunction "K_1") (pintype "unspecified"))
      (node (ref "LED11") (pin "2") (pinfunction "K_2") (pintype "unspecified"))
      (node (ref "LED12") (pin "2") (pinfunction "K_2") (pintype "unspecified"))
      (node (ref "LED13") (pin "2") (pinfunction "K_2") (pintype "unspecified"))
      (node (ref "LED14") (pin "2") (pinfunction "K_2") (pintype "unspecified"))
      (node (ref "LED3") (pin "2") (pinfunction "K_2") (pintype "unspecified"))
      (node (ref "LED4") (pin "2") (pinfunction "K_2") (pintype "unspecified"))
      (node (ref "LED5") (pin "2") (pinfunction "K_2") (pintype "unspecified"))
      (node (ref "LED6") (pin "2") (pinfunction "K_2") (pintype "unspecified"))
      (node (ref "LED7") (pin "2") (pinfunction "K_2") (pintype "unspecified"))
      (node (ref "LED8") (pin "2") (pinfunction "K_2") (pintype "unspecified"))
      (node (ref "LED9") (pin "1") (pinfunction "K_1") (pintype "unspecified"))
      (node (ref "P1") (pin "1") (pinfunction "1_1") (pintype "input"))
      (node (ref "P3") (pin "1") (pinfunction "1_1") (pintype "input"))
      (node (ref "P5") (pin "1") (pinfunction "1_1") (pintype "input"))
      (node (ref "POT1") (pin "1") (pinfunction "1_1") (pintype "input"))
      (node (ref "POT2") (pin "1") (pinfunction "1_1") (pintype "input"))
      (node (ref "R1") (pin "1") (pinfunction "1_1") (pintype "input"))
      (node (ref "R10") (pin "1") (pinfunction "1_1") (pintype "input"))
      (node (ref "R11") (pin "1") (pinfunction "1_1") (pintype "input"))
      (node (ref "R12") (pin "1") (pinfunction "1_1") (pintype "input"))
      (node (ref "R13") (pin "1") (pinfunction "1_1") (pintype "input"))
      (node (ref "R14") (pin "1") (pinfunction "1_1") (pintype "input"))
      (node (ref "R15") (pin "1") (pinfunction "1_1") (pintype "input"))
      (node (ref "R16") (pin "1") (pinfunction "1_1") (pintype "input"))
      (node (ref "R2") (pin "1") (pinfunction "1_1") (pintype "input"))
      (node (ref "R24") (pin "1") (pinfunction "1_1") (pintype "input"))
      (node (ref "R25") (pin "1") (pinfunction "1_1") (pintype "unspecified"))
      (node (ref "R28") (pin "1") (pinfunction "1_1") (pintype "input"))
      (node (ref "R3") (pin "1") (pinfunction "1_1") (pintype "input"))
      (node (ref "R31") (pin "1") (pinfunction "1_1") (pintype "input"))
      (node (ref "R32") (pin "1") (pinfunction "1_1") (pintype "input"))
      (node (ref "R37") (pin "1") (pinfunction "1_1") (pintype "input"))
      (node (ref "R4") (pin "1") (pinfunction "1_1") (pintype "input"))
      (node (ref "R45") (pin "1") (pinfunction "1_1") (pintype "input"))
      (node (ref "R46") (pin "1") (pinfunction "1_1") (pintype "input"))
      (node (ref "R5") (pin "1") (pinfunction "1_1") (pintype "input"))
      (node (ref "R57") (pin "1") (pinfunction "1_1") (pintype "input"))
      (node (ref "R58") (pin "1") (pinfunction "1_1") (pintype "input"))
      (node (ref "R59") (pin "1") (pinfunction "1_1") (pintype "input"))
      (node (ref "R6") (pin "1") (pinfunction "1_1") (pintype "input"))
      (node (ref "R7") (pin "1") (pinfunction "1_1") (pintype "input"))
      (node (ref "R8") (pin "1") (pinfunction "1_1") (pintype "input"))
      (node (ref "R9") (pin "1") (pinfunction "1_1") (pintype "input"))
      (node (ref "SHIFT_REG1") (pin "13") (pinfunction "OE#_13") (pintype "unspecified"))
      (node (ref "SHIFT_REG1") (pin "8") (pinfunction "GND_8") (pintype "unspecified"))
      (node (ref "U1") (pin "1") (pinfunction "VSS_1") (pintype "passive"))
      (node (ref "U1") (pin "16") (pinfunction "K_16") (pintype "passive"))
      (node (ref "U10") (pin "11") (pinfunction "GND_11") (pintype "unspecified"))
      (node (ref "U10") (pin "12") (pinfunction "GND_12") (pintype "unspecified"))
      (node (ref "U10") (pin "13") (pinfunction "GND_13") (pintype "unspecified"))
      (node (ref "U12") (pin "11") (pinfunction "GND_11") (pintype "unspecified"))
      (node (ref "U12") (pin "12") (pinfunction "GND_12") (pintype "unspecified"))
      (node (ref "U12") (pin "13") (pinfunction "GND_13") (pintype "unspecified"))
      (node (ref "U2") (pin "3") (pinfunction "G1_3") (pintype "unspecified"))
      (node (ref "U2") (pin "8") (pinfunction "G2_8") (pintype "unspecified"))
      (node (ref "U4") (pin "25") (pinfunction "GND_25") (pintype "unspecified"))
      (node (ref "U6") (pin "3") (pinfunction "G1_3") (pintype "unspecified"))
      (node (ref "U6") (pin "8") (pinfunction "G2_8") (pintype "unspecified"))
      (node (ref "U7") (pin "3") (pinfunction "GND_3") (pintype "unspecified"))
      (node (ref "U8") (pin "11") (pinfunction "GND_11") (pintype "unspecified"))
      (node (ref "U8") (pin "12") (pinfunction "GND_12") (pintype "unspecified"))
      (node (ref "U8") (pin "13") (pinfunction "GND_13") (pintype "unspecified"))
      (node (ref "U9") (pin "5") (pinfunction "VSS_5") (pintype "unspecified"))
      (node (ref "USB_C1") (pin "0") (pinfunction "SH_0") (pintype "unspecified"))
      (node (ref "USB_C1") (pin "1") (pinfunction "SH_1") (pintype "unspecified"))
      (node (ref "USB_C1") (pin "2") (pinfunction "SH_2") (pintype "unspecified"))
      (node (ref "USB_C1") (pin "3") (pinfunction "SH_3") (pintype "unspecified"))
      (node (ref "USB_C1") (pin "A1") (pinfunction "GND_A1") (pintype "unspecified"))
      (node (ref "USB_C1") (pin "A12") (pinfunction "GND_A12") (pintype "unspecified"))
      (node (ref "USB_C1") (pin "B1") (pinfunction "GND_B1") (pintype "unspecified"))
      (node (ref "USB_C1") (pin "B12") (pinfunction "GND_B12") (pintype "unspecified"))
      (node (ref "X2") (pin "2") (pinfunction "GND_2") (pintype "input"))
      (node (ref "X2") (pin "4") (pinfunction "GND_4") (pintype "input"))
    )
    (net (code "59") (name "IO_0") (class "Default")
      (node (ref "J1") (pin "25") (pinfunction "25_25") (pintype "bidirectional"))
      (node (ref "U12") (pin "14") (pinfunction "B8_14") (pintype "unspecified"))
    )
    (net (code "60") (name "IO_1") (class "Default")
      (node (ref "J1") (pin "26") (pinfunction "26_26") (pintype "bidirectional"))
      (node (ref "U12") (pin "15") (pinfunction "B7_15") (pintype "unspecified"))
    )
    (net (code "61") (name "IO_2") (class "Default")
      (node (ref "J1") (pin "27") (pinfunction "27_27") (pintype "bidirectional"))
      (node (ref "U12") (pin "16") (pinfunction "B6_16") (pintype "unspecified"))
    )
    (net (code "62") (name "IO_3") (class "Default")
      (node (ref "J1") (pin "1") (pinfunction "1_1") (pintype "bidirectional"))
      (node (ref "U12") (pin "17") (pinfunction "B5_17") (pintype "unspecified"))
    )
    (net (code "63") (name "IO_4") (class "Default")
      (node (ref "J1") (pin "2") (pinfunction "2_2") (pintype "bidirectional"))
      (node (ref "U12") (pin "18") (pinfunction "B4_18") (pintype "unspecified"))
    )
    (net (code "64") (name "IO_5") (class "Default")
      (node (ref "J1") (pin "3") (pinfunction "3_3") (pintype "bidirectional"))
      (node (ref "U12") (pin "19") (pinfunction "B3_19") (pintype "unspecified"))
    )
    (net (code "65") (name "IO_6") (class "Default")
      (node (ref "J1") (pin "4") (pinfunction "4_4") (pintype "bidirectional"))
      (node (ref "U12") (pin "20") (pinfunction "B2_20") (pintype "unspecified"))
    )
    (net (code "66") (name "IO_7") (class "Default")
      (node (ref "J1") (pin "5") (pinfunction "5_5") (pintype "bidirectional"))
      (node (ref "U12") (pin "21") (pinfunction "B1_21") (pintype "unspecified"))
    )
    (net (code "67") (name "LCD_D4") (class "Default")
      (node (ref "JP7") (pin "5") (pinfunction "5_5") (pintype "unspecified"))
      (node (ref "LCD1") (pin "11") (pinfunction "DB4_11") (pintype "unspecified"))
      (node (ref "U1") (pin "11") (pinfunction "DB4_11") (pintype "unspecified"))
    )
    (net (code "68") (name "LCD_D5") (class "Default")
      (node (ref "JP7") (pin "4") (pinfunction "4_4") (pintype "unspecified"))
      (node (ref "LCD1") (pin "12") (pinfunction "DB5_12") (pintype "unspecified"))
      (node (ref "U1") (pin "12") (pinfunction "DB5_12") (pintype "unspecified"))
    )
    (net (code "69") (name "LCD_D6") (class "Default")
      (node (ref "JP7") (pin "3") (pinfunction "3_3") (pintype "unspecified"))
      (node (ref "LCD1") (pin "13") (pinfunction "DB6_13") (pintype "unspecified"))
      (node (ref "U1") (pin "13") (pinfunction "DB6_13") (pintype "unspecified"))
    )
    (net (code "70") (name "LCD_D7") (class "Default")
      (node (ref "JP7") (pin "2") (pinfunction "2_2") (pintype "unspecified"))
      (node (ref "LCD1") (pin "14") (pinfunction "DB7_14") (pintype "unspecified"))
      (node (ref "U1") (pin "14") (pinfunction "DB7_14") (pintype "unspecified"))
    )
    (net (code "71") (name "LCD_E") (class "Default")
      (node (ref "JP7") (pin "6") (pinfunction "6_6") (pintype "unspecified"))
      (node (ref "LCD1") (pin "6") (pinfunction "E_6") (pintype "unspecified"))
      (node (ref "U1") (pin "6") (pinfunction "E_6") (pintype "input"))
    )
    (net (code "72") (name "LCD_RS") (class "Default")
      (node (ref "JP7") (pin "8") (pinfunction "8_8") (pintype "unspecified"))
      (node (ref "LCD1") (pin "4") (pinfunction "RS_4") (pintype "unspecified"))
      (node (ref "U1") (pin "4") (pinfunction "RS_4") (pintype "input"))
    )
    (net (code "73") (name "LCD_RW") (class "Default")
      (node (ref "JP7") (pin "7") (pinfunction "7_7") (pintype "unspecified"))
      (node (ref "LCD1") (pin "5") (pinfunction "R/W_5") (pintype "unspecified"))
      (node (ref "U1") (pin "5") (pinfunction "RW_5") (pintype "input"))
    )
    (net (code "74") (name "LCD_V_o") (class "Default")
      (node (ref "LCD1") (pin "3") (pinfunction "VO_3") (pintype "unspecified"))
      (node (ref "P2") (pin "1") (pinfunction "1_1") (pintype "input"))
      (node (ref "R25") (pin "2") (pinfunction "2_2") (pintype "unspecified"))
      (node (ref "U1") (pin "3") (pinfunction "VO_3") (pintype "unspecified"))
    )
    (net (code "75") (name "LED1") (class "Default")
      (node (ref "JP3") (pin "8") (pinfunction "8_8") (pintype "unspecified"))
      (node (ref "R47") (pin "2") (pinfunction "2_2") (pintype "input"))
    )
    (net (code "76") (name "LED2") (class "Default")
      (node (ref "JP3") (pin "7") (pinfunction "7_7") (pintype "unspecified"))
      (node (ref "R17") (pin "2") (pinfunction "2_2") (pintype "input"))
    )
    (net (code "77") (name "LED3") (class "Default")
      (node (ref "JP3") (pin "6") (pinfunction "6_6") (pintype "unspecified"))
      (node (ref "R19") (pin "2") (pinfunction "2_2") (pintype "input"))
    )
    (net (code "78") (name "LED4") (class "Default")
      (node (ref "JP3") (pin "5") (pinfunction "5_5") (pintype "unspecified"))
      (node (ref "R18") (pin "2") (pinfunction "2_2") (pintype "input"))
    )
    (net (code "79") (name "LED5") (class "Default")
      (node (ref "JP3") (pin "4") (pinfunction "4_4") (pintype "unspecified"))
      (node (ref "R21") (pin "2") (pinfunction "2_2") (pintype "input"))
    )
    (net (code "80") (name "LED6") (class "Default")
      (node (ref "JP3") (pin "3") (pinfunction "3_3") (pintype "unspecified"))
      (node (ref "R20") (pin "2") (pinfunction "2_2") (pintype "input"))
    )
    (net (code "81") (name "LED7") (class "Default")
      (node (ref "JP3") (pin "2") (pinfunction "2_2") (pintype "unspecified"))
      (node (ref "R23") (pin "2") (pinfunction "2_2") (pintype "input"))
    )
    (net (code "82") (name "LED8") (class "Default")
      (node (ref "JP3") (pin "1") (pinfunction "1_1") (pintype "unspecified"))
      (node (ref "R22") (pin "2") (pinfunction "2_2") (pintype "input"))
    )
    (net (code "83") (name "MCLR") (class "Default")
      (node (ref "C5") (pin "2") (pinfunction "2_2") (pintype "input"))
      (node (ref "HR_B2") (pin "23") (pinfunction "23_23") (pintype "unspecified"))
      (node (ref "MCLR") (pin "3") (pinfunction "C_3") (pintype "unspecified"))
      (node (ref "MCLR") (pin "4") (pinfunction "D_4") (pintype "unspecified"))
      (node (ref "R31") (pin "2") (pinfunction "2_2") (pintype "input"))
      (node (ref "U4") (pin "26") (pinfunction "26_26") (pintype "unspecified"))
    )
    (net (code "84") (name "MISO") (class "Default")
      (node (ref "JP8") (pin "4") (pinfunction "4_4") (pintype "unspecified"))
      (node (ref "U9") (pin "4") (pinfunction "DO_4") (pintype "unspecified"))
    )
    (net (code "85") (name "MOSI") (class "Default")
      (node (ref "JP8") (pin "5") (pinfunction "5_5") (pintype "unspecified"))
      (node (ref "U9") (pin "3") (pinfunction "DI_3") (pintype "unspecified"))
    )
    (net (code "86") (name "Net-(CH1G-XI)") (class "Default")
      (node (ref "C12") (pin "2") (pinfunction "2_2") (pintype "input"))
      (node (ref "CH1G") (pin "7") (pinfunction "XI_7") (pintype "unspecified"))
      (node (ref "X2") (pin "1") (pinfunction "1_1") (pintype "input"))
    )
    (net (code "87") (name "Net-(CH1G-XO)") (class "Default")
      (node (ref "C11") (pin "2") (pinfunction "2_2") (pintype "input"))
      (node (ref "CH1G") (pin "8") (pinfunction "XO_8") (pintype "unspecified"))
      (node (ref "X2") (pin "3") (pinfunction "3_3") (pintype "input"))
    )
    (net (code "88") (name "Net-(DEV1-+5V-Pad40)") (class "Default")
      (node (ref "DEV1") (pin "40") (pinfunction "+5V_40") (pintype "unspecified"))
      (node (ref "P8") (pin "2") (pinfunction "2_2") (pintype "unspecified"))
    )
    (net (code "89") (name "Net-(EEPROM1-A0)") (class "Default")
      (node (ref "EEPROM1") (pin "1") (pinfunction "NC_1") (pintype "unspecified"))
      (node (ref "EEPROM1") (pin "10") (pinfunction "A0_10") (pintype "unspecified"))
      (node (ref "EEPROM1") (pin "11") (pinfunction "IO0_11") (pintype "unspecified"))
      (node (ref "EEPROM1") (pin "12") (pinfunction "IO1_12") (pintype "unspecified"))
      (node (ref "EEPROM1") (pin "13") (pinfunction "IO2_13") (pintype "unspecified"))
      (node (ref "EEPROM1") (pin "14") (pinfunction "GND_14") (pintype "unspecified"))
      (node (ref "EEPROM1") (pin "15") (pinfunction "IO3_15") (pintype "unspecified"))
      (node (ref "EEPROM1") (pin "16") (pinfunction "IO4_16") (pintype "unspecified"))
      (node (ref "EEPROM1") (pin "17") (pinfunction "IO5_17") (pintype "unspecified"))
      (node (ref "EEPROM1") (pin "18") (pinfunction "IO6_18") (pintype "unspecified"))
      (node (ref "EEPROM1") (pin "19") (pinfunction "IO7_19") (pintype "unspecified"))
      (node (ref "EEPROM1") (pin "2") (pinfunction "A12_2") (pintype "unspecified"))
      (node (ref "EEPROM1") (pin "20") (pinfunction "CE#_20") (pintype "unspecified"))
      (node (ref "EEPROM1") (pin "21") (pinfunction "A10_21") (pintype "unspecified"))
      (node (ref "EEPROM1") (pin "22") (pinfunction "OE#_22") (pintype "unspecified"))
      (node (ref "EEPROM1") (pin "23") (pinfunction "A11_23") (pintype "unspecified"))
      (node (ref "EEPROM1") (pin "24") (pinfunction "A9_24") (pintype "unspecified"))
      (node (ref "EEPROM1") (pin "25") (pinfunction "A8_25") (pintype "unspecified"))
      (node (ref "EEPROM1") (pin "26") (pinfunction "NC_26") (pintype "unspecified"))
      (node (ref "EEPROM1") (pin "27") (pinfunction "WE#_27") (pintype "unspecified"))
      (node (ref "EEPROM1") (pin "28") (pinfunction "VCC_28") (pintype "unspecified"))
      (node (ref "EEPROM1") (pin "3") (pinfunction "A7_3") (pintype "unspecified"))
      (node (ref "EEPROM1") (pin "4") (pinfunction "A6_4") (pintype "unspecified"))
      (node (ref "EEPROM1") (pin "5") (pinfunction "A5_5") (pintype "unspecified"))
      (node (ref "EEPROM1") (pin "6") (pinfunction "A4_6") (pintype "unspecified"))
      (node (ref "EEPROM1") (pin "7") (pinfunction "A3_7") (pintype "unspecified"))
      (node (ref "EEPROM1") (pin "8") (pinfunction "A2_8") (pintype "unspecified"))
      (node (ref "EEPROM1") (pin "9") (pinfunction "A1_9") (pintype "unspecified"))
    )
    (net (code "90") (name "Net-(H1-Pad10)") (class "Default")
      (node (ref "H1") (pin "10") (pinfunction "10_10") (pintype "unspecified"))
      (node (ref "H1") (pin "12") (pinfunction "12_12") (pintype "unspecified"))
      (node (ref "H1") (pin "14") (pinfunction "14_14") (pintype "unspecified"))
      (node (ref "H1") (pin "16") (pinfunction "16_16") (pintype "unspecified"))
      (node (ref "H1") (pin "18") (pinfunction "18_18") (pintype "unspecified"))
      (node (ref "H1") (pin "6") (pinfunction "6_6") (pintype "unspecified"))
      (node (ref "H1") (pin "8") (pinfunction "8_8") (pintype "unspecified"))
    )
    (net (code "91") (name "Net-(H1-Pad11)") (class "Default")
      (node (ref "H1") (pin "11") (pinfunction "11_11") (pintype "unspecified"))
      (node (ref "H1") (pin "13") (pinfunction "13_13") (pintype "unspecified"))
      (node (ref "H1") (pin "15") (pinfunction "15_15") (pintype "unspecified"))
      (node (ref "H1") (pin "17") (pinfunction "17_17") (pintype "unspecified"))
      (node (ref "H1") (pin "5") (pinfunction "5_5") (pintype "unspecified"))
      (node (ref "H1") (pin "7") (pinfunction "7_7") (pintype "unspecified"))
      (node (ref "H1") (pin "9") (pinfunction "9_9") (pintype "unspecified"))
    )
    (net (code "92") (name "Net-(H1-Pad19)") (class "Default")
      (node (ref "H1") (pin "19") (pinfunction "19_19") (pintype "unspecified"))
      (node (ref "H1") (pin "21") (pinfunction "21_21") (pintype "unspecified"))
      (node (ref "H1") (pin "23") (pinfunction "23_23") (pintype "unspecified"))
      (node (ref "H1") (pin "25") (pinfunction "25_25") (pintype "unspecified"))
      (node (ref "H1") (pin "27") (pinfunction "27_27") (pintype "unspecified"))
      (node (ref "H1") (pin "29") (pinfunction "29_29") (pintype "unspecified"))
    )
    (net (code "93") (name "Net-(H1-Pad20)") (class "Default")
      (node (ref "H1") (pin "20") (pinfunction "20_20") (pintype "unspecified"))
      (node (ref "H1") (pin "22") (pinfunction "22_22") (pintype "unspecified"))
      (node (ref "H1") (pin "24") (pinfunction "24_24") (pintype "unspecified"))
      (node (ref "H1") (pin "26") (pinfunction "26_26") (pintype "unspecified"))
      (node (ref "H1") (pin "28") (pinfunction "28_28") (pintype "unspecified"))
      (node (ref "H1") (pin "30") (pinfunction "30_30") (pintype "unspecified"))
    )
    (net (code "94") (name "Net-(H1-Pad31)") (class "Default")
      (node (ref "H1") (pin "31") (pinfunction "31_31") (pintype "unspecified"))
      (node (ref "H1") (pin "33") (pinfunction "33_33") (pintype "unspecified"))
      (node (ref "H1") (pin "35") (pinfunction "35_35") (pintype "unspecified"))
      (node (ref "H1") (pin "37") (pinfunction "37_37") (pintype "unspecified"))
      (node (ref "H1") (pin "39") (pinfunction "39_39") (pintype "unspecified"))
      (node (ref "H1") (pin "41") (pinfunction "41_41") (pintype "unspecified"))
      (node (ref "H1") (pin "43") (pinfunction "43_43") (pintype "unspecified"))
    )
    (net (code "95") (name "Net-(H1-Pad32)") (class "Default")
      (node (ref "H1") (pin "32") (pinfunction "32_32") (pintype "unspecified"))
      (node (ref "H1") (pin "34") (pinfunction "34_34") (pintype "unspecified"))
      (node (ref "H1") (pin "36") (pinfunction "36_36") (pintype "unspecified"))
      (node (ref "H1") (pin "38") (pinfunction "38_38") (pintype "unspecified"))
      (node (ref "H1") (pin "40") (pinfunction "40_40") (pintype "unspecified"))
      (node (ref "H1") (pin "42") (pinfunction "42_42") (pintype "unspecified"))
      (node (ref "H1") (pin "44") (pinfunction "44_44") (pintype "unspecified"))
    )
    (net (code "96") (name "Net-(H2-Pad10)") (class "Default")
      (node (ref "H2") (pin "10") (pinfunction "10_10") (pintype "unspecified"))
      (node (ref "H2") (pin "12") (pinfunction "12_12") (pintype "unspecified"))
      (node (ref "H2") (pin "14") (pinfunction "14_14") (pintype "unspecified"))
      (node (ref "H2") (pin "16") (pinfunction "16_16") (pintype "unspecified"))
      (node (ref "H2") (pin "18") (pinfunction "18_18") (pintype "unspecified"))
      (node (ref "H2") (pin "6") (pinfunction "6_6") (pintype "unspecified"))
      (node (ref "H2") (pin "8") (pinfunction "8_8") (pintype "unspecified"))
    )
    (net (code "97") (name "Net-(H2-Pad11)") (class "Default")
      (node (ref "H2") (pin "11") (pinfunction "11_11") (pintype "unspecified"))
      (node (ref "H2") (pin "13") (pinfunction "13_13") (pintype "unspecified"))
      (node (ref "H2") (pin "15") (pinfunction "15_15") (pintype "unspecified"))
      (node (ref "H2") (pin "17") (pinfunction "17_17") (pintype "unspecified"))
      (node (ref "H2") (pin "5") (pinfunction "5_5") (pintype "unspecified"))
      (node (ref "H2") (pin "7") (pinfunction "7_7") (pintype "unspecified"))
      (node (ref "H2") (pin "9") (pinfunction "9_9") (pintype "unspecified"))
    )
    (net (code "98") (name "Net-(H2-Pad19)") (class "Default")
      (node (ref "H2") (pin "19") (pinfunction "19_19") (pintype "unspecified"))
      (node (ref "H2") (pin "21") (pinfunction "21_21") (pintype "unspecified"))
      (node (ref "H2") (pin "23") (pinfunction "23_23") (pintype "unspecified"))
      (node (ref "H2") (pin "25") (pinfunction "25_25") (pintype "unspecified"))
      (node (ref "H2") (pin "27") (pinfunction "27_27") (pintype "unspecified"))
      (node (ref "H2") (pin "29") (pinfunction "29_29") (pintype "unspecified"))
    )
    (net (code "99") (name "Net-(H2-Pad20)") (class "Default")
      (node (ref "H2") (pin "20") (pinfunction "20_20") (pintype "unspecified"))
      (node (ref "H2") (pin "22") (pinfunction "22_22") (pintype "unspecified"))
      (node (ref "H2") (pin "24") (pinfunction "24_24") (pintype "unspecified"))
      (node (ref "H2") (pin "26") (pinfunction "26_26") (pintype "unspecified"))
      (node (ref "H2") (pin "28") (pinfunction "28_28") (pintype "unspecified"))
      (node (ref "H2") (pin "30") (pinfunction "30_30") (pintype "unspecified"))
    )
    (net (code "100") (name "Net-(H2-Pad31)") (class "Default")
      (node (ref "H2") (pin "31") (pinfunction "31_31") (pintype "unspecified"))
      (node (ref "H2") (pin "33") (pinfunction "33_33") (pintype "unspecified"))
      (node (ref "H2") (pin "35") (pinfunction "35_35") (pintype "unspecified"))
      (node (ref "H2") (pin "37") (pinfunction "37_37") (pintype "unspecified"))
      (node (ref "H2") (pin "39") (pinfunction "39_39") (pintype "unspecified"))
      (node (ref "H2") (pin "41") (pinfunction "41_41") (pintype "unspecified"))
      (node (ref "H2") (pin "43") (pinfunction "43_43") (pintype "unspecified"))
    )
    (net (code "101") (name "Net-(H2-Pad32)") (class "Default")
      (node (ref "H2") (pin "32") (pinfunction "32_32") (pintype "unspecified"))
      (node (ref "H2") (pin "34") (pinfunction "34_34") (pintype "unspecified"))
      (node (ref "H2") (pin "36") (pinfunction "36_36") (pintype "unspecified"))
      (node (ref "H2") (pin "38") (pinfunction "38_38") (pintype "unspecified"))
      (node (ref "H2") (pin "40") (pinfunction "40_40") (pintype "unspecified"))
      (node (ref "H2") (pin "42") (pinfunction "42_42") (pintype "unspecified"))
      (node (ref "H2") (pin "44") (pinfunction "44_44") (pintype "unspecified"))
    )
    (net (code "102") (name "Net-(H3-Pad10)") (class "Default")
      (node (ref "H3") (pin "10") (pinfunction "10_10") (pintype "unspecified"))
      (node (ref "H3") (pin "12") (pinfunction "12_12") (pintype "unspecified"))
      (node (ref "H3") (pin "14") (pinfunction "14_14") (pintype "unspecified"))
      (node (ref "H3") (pin "16") (pinfunction "16_16") (pintype "unspecified"))
      (node (ref "H3") (pin "18") (pinfunction "18_18") (pintype "unspecified"))
      (node (ref "H3") (pin "6") (pinfunction "6_6") (pintype "unspecified"))
      (node (ref "H3") (pin "8") (pinfunction "8_8") (pintype "unspecified"))
    )
    (net (code "103") (name "Net-(H3-Pad11)") (class "Default")
      (node (ref "H3") (pin "11") (pinfunction "11_11") (pintype "unspecified"))
      (node (ref "H3") (pin "13") (pinfunction "13_13") (pintype "unspecified"))
      (node (ref "H3") (pin "15") (pinfunction "15_15") (pintype "unspecified"))
      (node (ref "H3") (pin "17") (pinfunction "17_17") (pintype "unspecified"))
      (node (ref "H3") (pin "5") (pinfunction "5_5") (pintype "unspecified"))
      (node (ref "H3") (pin "7") (pinfunction "7_7") (pintype "unspecified"))
      (node (ref "H3") (pin "9") (pinfunction "9_9") (pintype "unspecified"))
    )
    (net (code "104") (name "Net-(H3-Pad19)") (class "Default")
      (node (ref "H3") (pin "19") (pinfunction "19_19") (pintype "unspecified"))
      (node (ref "H3") (pin "21") (pinfunction "21_21") (pintype "unspecified"))
      (node (ref "H3") (pin "23") (pinfunction "23_23") (pintype "unspecified"))
      (node (ref "H3") (pin "25") (pinfunction "25_25") (pintype "unspecified"))
      (node (ref "H3") (pin "27") (pinfunction "27_27") (pintype "unspecified"))
      (node (ref "H3") (pin "29") (pinfunction "29_29") (pintype "unspecified"))
    )
    (net (code "105") (name "Net-(H3-Pad20)") (class "Default")
      (node (ref "H3") (pin "20") (pinfunction "20_20") (pintype "unspecified"))
      (node (ref "H3") (pin "22") (pinfunction "22_22") (pintype "unspecified"))
      (node (ref "H3") (pin "24") (pinfunction "24_24") (pintype "unspecified"))
      (node (ref "H3") (pin "26") (pinfunction "26_26") (pintype "unspecified"))
      (node (ref "H3") (pin "28") (pinfunction "28_28") (pintype "unspecified"))
      (node (ref "H3") (pin "30") (pinfunction "30_30") (pintype "unspecified"))
    )
    (net (code "106") (name "Net-(H3-Pad31)") (class "Default")
      (node (ref "H3") (pin "31") (pinfunction "31_31") (pintype "unspecified"))
      (node (ref "H3") (pin "33") (pinfunction "33_33") (pintype "unspecified"))
      (node (ref "H3") (pin "35") (pinfunction "35_35") (pintype "unspecified"))
      (node (ref "H3") (pin "37") (pinfunction "37_37") (pintype "unspecified"))
      (node (ref "H3") (pin "39") (pinfunction "39_39") (pintype "unspecified"))
      (node (ref "H3") (pin "41") (pinfunction "41_41") (pintype "unspecified"))
      (node (ref "H3") (pin "43") (pinfunction "43_43") (pintype "unspecified"))
    )
    (net (code "107") (name "Net-(H3-Pad32)") (class "Default")
      (node (ref "H3") (pin "32") (pinfunction "32_32") (pintype "unspecified"))
      (node (ref "H3") (pin "34") (pinfunction "34_34") (pintype "unspecified"))
      (node (ref "H3") (pin "36") (pinfunction "36_36") (pintype "unspecified"))
      (node (ref "H3") (pin "38") (pinfunction "38_38") (pintype "unspecified"))
      (node (ref "H3") (pin "40") (pinfunction "40_40") (pintype "unspecified"))
      (node (ref "H3") (pin "42") (pinfunction "42_42") (pintype "unspecified"))
      (node (ref "H3") (pin "44") (pinfunction "44_44") (pintype "unspecified"))
    )
    (net (code "108") (name "Net-(H4-Pad10)") (class "Default")
      (node (ref "H4") (pin "10") (pinfunction "10_10") (pintype "unspecified"))
      (node (ref "H4") (pin "12") (pinfunction "12_12") (pintype "unspecified"))
      (node (ref "H4") (pin "14") (pinfunction "14_14") (pintype "unspecified"))
      (node (ref "H4") (pin "16") (pinfunction "16_16") (pintype "unspecified"))
      (node (ref "H4") (pin "18") (pinfunction "18_18") (pintype "unspecified"))
      (node (ref "H4") (pin "6") (pinfunction "6_6") (pintype "unspecified"))
      (node (ref "H4") (pin "8") (pinfunction "8_8") (pintype "unspecified"))
    )
    (net (code "109") (name "Net-(H4-Pad11)") (class "Default")
      (node (ref "H4") (pin "11") (pinfunction "11_11") (pintype "unspecified"))
      (node (ref "H4") (pin "13") (pinfunction "13_13") (pintype "unspecified"))
      (node (ref "H4") (pin "15") (pinfunction "15_15") (pintype "unspecified"))
      (node (ref "H4") (pin "17") (pinfunction "17_17") (pintype "unspecified"))
      (node (ref "H4") (pin "5") (pinfunction "5_5") (pintype "unspecified"))
      (node (ref "H4") (pin "7") (pinfunction "7_7") (pintype "unspecified"))
      (node (ref "H4") (pin "9") (pinfunction "9_9") (pintype "unspecified"))
    )
    (net (code "110") (name "Net-(H4-Pad19)") (class "Default")
      (node (ref "H4") (pin "19") (pinfunction "19_19") (pintype "unspecified"))
      (node (ref "H4") (pin "21") (pinfunction "21_21") (pintype "unspecified"))
      (node (ref "H4") (pin "23") (pinfunction "23_23") (pintype "unspecified"))
      (node (ref "H4") (pin "25") (pinfunction "25_25") (pintype "unspecified"))
      (node (ref "H4") (pin "27") (pinfunction "27_27") (pintype "unspecified"))
      (node (ref "H4") (pin "29") (pinfunction "29_29") (pintype "unspecified"))
    )
    (net (code "111") (name "Net-(H4-Pad20)") (class "Default")
      (node (ref "H4") (pin "20") (pinfunction "20_20") (pintype "unspecified"))
      (node (ref "H4") (pin "22") (pinfunction "22_22") (pintype "unspecified"))
      (node (ref "H4") (pin "24") (pinfunction "24_24") (pintype "unspecified"))
      (node (ref "H4") (pin "26") (pinfunction "26_26") (pintype "unspecified"))
      (node (ref "H4") (pin "28") (pinfunction "28_28") (pintype "unspecified"))
      (node (ref "H4") (pin "30") (pinfunction "30_30") (pintype "unspecified"))
    )
    (net (code "112") (name "Net-(H4-Pad31)") (class "Default")
      (node (ref "H4") (pin "31") (pinfunction "31_31") (pintype "unspecified"))
      (node (ref "H4") (pin "33") (pinfunction "33_33") (pintype "unspecified"))
      (node (ref "H4") (pin "35") (pinfunction "35_35") (pintype "unspecified"))
      (node (ref "H4") (pin "37") (pinfunction "37_37") (pintype "unspecified"))
      (node (ref "H4") (pin "39") (pinfunction "39_39") (pintype "unspecified"))
      (node (ref "H4") (pin "41") (pinfunction "41_41") (pintype "unspecified"))
      (node (ref "H4") (pin "43") (pinfunction "43_43") (pintype "unspecified"))
    )
    (net (code "113") (name "Net-(H4-Pad32)") (class "Default")
      (node (ref "H4") (pin "32") (pinfunction "32_32") (pintype "unspecified"))
      (node (ref "H4") (pin "34") (pinfunction "34_34") (pintype "unspecified"))
      (node (ref "H4") (pin "36") (pinfunction "36_36") (pintype "unspecified"))
      (node (ref "H4") (pin "38") (pinfunction "38_38") (pintype "unspecified"))
      (node (ref "H4") (pin "40") (pinfunction "40_40") (pintype "unspecified"))
      (node (ref "H4") (pin "42") (pinfunction "42_42") (pintype "unspecified"))
      (node (ref "H4") (pin "44") (pinfunction "44_44") (pintype "unspecified"))
    )
    (net (code "114") (name "Net-(H5-Pad10)") (class "Default")
      (node (ref "H5") (pin "10") (pinfunction "10_10") (pintype "unspecified"))
      (node (ref "H5") (pin "12") (pinfunction "12_12") (pintype "unspecified"))
      (node (ref "H5") (pin "14") (pinfunction "14_14") (pintype "unspecified"))
      (node (ref "H5") (pin "16") (pinfunction "16_16") (pintype "unspecified"))
      (node (ref "H5") (pin "18") (pinfunction "18_18") (pintype "unspecified"))
      (node (ref "H5") (pin "6") (pinfunction "6_6") (pintype "unspecified"))
      (node (ref "H5") (pin "8") (pinfunction "8_8") (pintype "unspecified"))
    )
    (net (code "115") (name "Net-(H5-Pad11)") (class "Default")
      (node (ref "H5") (pin "11") (pinfunction "11_11") (pintype "unspecified"))
      (node (ref "H5") (pin "13") (pinfunction "13_13") (pintype "unspecified"))
      (node (ref "H5") (pin "15") (pinfunction "15_15") (pintype "unspecified"))
      (node (ref "H5") (pin "17") (pinfunction "17_17") (pintype "unspecified"))
      (node (ref "H5") (pin "5") (pinfunction "5_5") (pintype "unspecified"))
      (node (ref "H5") (pin "7") (pinfunction "7_7") (pintype "unspecified"))
      (node (ref "H5") (pin "9") (pinfunction "9_9") (pintype "unspecified"))
    )
    (net (code "116") (name "Net-(H5-Pad19)") (class "Default")
      (node (ref "H5") (pin "19") (pinfunction "19_19") (pintype "unspecified"))
      (node (ref "H5") (pin "21") (pinfunction "21_21") (pintype "unspecified"))
      (node (ref "H5") (pin "23") (pinfunction "23_23") (pintype "unspecified"))
      (node (ref "H5") (pin "25") (pinfunction "25_25") (pintype "unspecified"))
      (node (ref "H5") (pin "27") (pinfunction "27_27") (pintype "unspecified"))
      (node (ref "H5") (pin "29") (pinfunction "29_29") (pintype "unspecified"))
    )
    (net (code "117") (name "Net-(H5-Pad20)") (class "Default")
      (node (ref "H5") (pin "20") (pinfunction "20_20") (pintype "unspecified"))
      (node (ref "H5") (pin "22") (pinfunction "22_22") (pintype "unspecified"))
      (node (ref "H5") (pin "24") (pinfunction "24_24") (pintype "unspecified"))
      (node (ref "H5") (pin "26") (pinfunction "26_26") (pintype "unspecified"))
      (node (ref "H5") (pin "28") (pinfunction "28_28") (pintype "unspecified"))
      (node (ref "H5") (pin "30") (pinfunction "30_30") (pintype "unspecified"))
    )
    (net (code "118") (name "Net-(H5-Pad31)") (class "Default")
      (node (ref "H5") (pin "31") (pinfunction "31_31") (pintype "unspecified"))
      (node (ref "H5") (pin "33") (pinfunction "33_33") (pintype "unspecified"))
      (node (ref "H5") (pin "35") (pinfunction "35_35") (pintype "unspecified"))
      (node (ref "H5") (pin "37") (pinfunction "37_37") (pintype "unspecified"))
      (node (ref "H5") (pin "39") (pinfunction "39_39") (pintype "unspecified"))
      (node (ref "H5") (pin "41") (pinfunction "41_41") (pintype "unspecified"))
      (node (ref "H5") (pin "43") (pinfunction "43_43") (pintype "unspecified"))
    )
    (net (code "119") (name "Net-(H5-Pad32)") (class "Default")
      (node (ref "H5") (pin "32") (pinfunction "32_32") (pintype "unspecified"))
      (node (ref "H5") (pin "34") (pinfunction "34_34") (pintype "unspecified"))
      (node (ref "H5") (pin "36") (pinfunction "36_36") (pintype "unspecified"))
      (node (ref "H5") (pin "38") (pinfunction "38_38") (pintype "unspecified"))
      (node (ref "H5") (pin "40") (pinfunction "40_40") (pintype "unspecified"))
      (node (ref "H5") (pin "42") (pinfunction "42_42") (pintype "unspecified"))
      (node (ref "H5") (pin "44") (pinfunction "44_44") (pintype "unspecified"))
    )
    (net (code "120") (name "Net-(H6-Pad10)") (class "Default")
      (node (ref "H6") (pin "10") (pinfunction "10_10") (pintype "unspecified"))
      (node (ref "H6") (pin "12") (pinfunction "12_12") (pintype "unspecified"))
      (node (ref "H6") (pin "14") (pinfunction "14_14") (pintype "unspecified"))
      (node (ref "H6") (pin "16") (pinfunction "16_16") (pintype "unspecified"))
      (node (ref "H6") (pin "18") (pinfunction "18_18") (pintype "unspecified"))
      (node (ref "H6") (pin "6") (pinfunction "6_6") (pintype "unspecified"))
      (node (ref "H6") (pin "8") (pinfunction "8_8") (pintype "unspecified"))
    )
    (net (code "121") (name "Net-(H6-Pad11)") (class "Default")
      (node (ref "H6") (pin "11") (pinfunction "11_11") (pintype "unspecified"))
      (node (ref "H6") (pin "13") (pinfunction "13_13") (pintype "unspecified"))
      (node (ref "H6") (pin "15") (pinfunction "15_15") (pintype "unspecified"))
      (node (ref "H6") (pin "17") (pinfunction "17_17") (pintype "unspecified"))
      (node (ref "H6") (pin "5") (pinfunction "5_5") (pintype "unspecified"))
      (node (ref "H6") (pin "7") (pinfunction "7_7") (pintype "unspecified"))
      (node (ref "H6") (pin "9") (pinfunction "9_9") (pintype "unspecified"))
    )
    (net (code "122") (name "Net-(H6-Pad19)") (class "Default")
      (node (ref "H6") (pin "19") (pinfunction "19_19") (pintype "unspecified"))
      (node (ref "H6") (pin "21") (pinfunction "21_21") (pintype "unspecified"))
      (node (ref "H6") (pin "23") (pinfunction "23_23") (pintype "unspecified"))
      (node (ref "H6") (pin "25") (pinfunction "25_25") (pintype "unspecified"))
      (node (ref "H6") (pin "27") (pinfunction "27_27") (pintype "unspecified"))
      (node (ref "H6") (pin "29") (pinfunction "29_29") (pintype "unspecified"))
    )
    (net (code "123") (name "Net-(H6-Pad20)") (class "Default")
      (node (ref "H6") (pin "20") (pinfunction "20_20") (pintype "unspecified"))
      (node (ref "H6") (pin "22") (pinfunction "22_22") (pintype "unspecified"))
      (node (ref "H6") (pin "24") (pinfunction "24_24") (pintype "unspecified"))
      (node (ref "H6") (pin "26") (pinfunction "26_26") (pintype "unspecified"))
      (node (ref "H6") (pin "28") (pinfunction "28_28") (pintype "unspecified"))
      (node (ref "H6") (pin "30") (pinfunction "30_30") (pintype "unspecified"))
    )
    (net (code "124") (name "Net-(H6-Pad31)") (class "Default")
      (node (ref "H6") (pin "31") (pinfunction "31_31") (pintype "unspecified"))
      (node (ref "H6") (pin "33") (pinfunction "33_33") (pintype "unspecified"))
      (node (ref "H6") (pin "35") (pinfunction "35_35") (pintype "unspecified"))
      (node (ref "H6") (pin "37") (pinfunction "37_37") (pintype "unspecified"))
      (node (ref "H6") (pin "39") (pinfunction "39_39") (pintype "unspecified"))
      (node (ref "H6") (pin "41") (pinfunction "41_41") (pintype "unspecified"))
      (node (ref "H6") (pin "43") (pinfunction "43_43") (pintype "unspecified"))
    )
    (net (code "125") (name "Net-(H6-Pad32)") (class "Default")
      (node (ref "H6") (pin "32") (pinfunction "32_32") (pintype "unspecified"))
      (node (ref "H6") (pin "34") (pinfunction "34_34") (pintype "unspecified"))
      (node (ref "H6") (pin "36") (pinfunction "36_36") (pintype "unspecified"))
      (node (ref "H6") (pin "38") (pinfunction "38_38") (pintype "unspecified"))
      (node (ref "H6") (pin "40") (pinfunction "40_40") (pintype "unspecified"))
      (node (ref "H6") (pin "42") (pinfunction "42_42") (pintype "unspecified"))
      (node (ref "H6") (pin "44") (pinfunction "44_44") (pintype "unspecified"))
    )
    (net (code "126") (name "Net-(JP7-Pad1)") (class "Default")
      (node (ref "JP7") (pin "1") (pinfunction "1_1") (pintype "unspecified"))
      (node (ref "R56") (pin "1") (pinfunction "1_1") (pintype "input"))
    )
    (net (code "127") (name "Net-(LCD1-BLA)") (class "Default")
      (node (ref "LCD1") (pin "15") (pinfunction "BLA_15") (pintype "unspecified"))
      (node (ref "R26") (pin "1") (pinfunction "1_1") (pintype "input"))
    )
    (net (code "128") (name "Net-(LED1-A)") (class "Default")
      (node (ref "LED1") (pin "1") (pinfunction "A_1") (pintype "unspecified"))
      (node (ref "R49") (pin "1") (pinfunction "1_1") (pintype "input"))
    )
    (net (code "129") (name "Net-(LED2-A)") (class "Default")
      (node (ref "LED2") (pin "1") (pinfunction "A_1") (pintype "unspecified"))
      (node (ref "R50") (pin "1") (pinfunction "1_1") (pintype "input"))
    )
    (net (code "130") (name "Net-(LED3-A)") (class "Default")
      (node (ref "LED3") (pin "1") (pinfunction "A_1") (pintype "unspecified"))
      (node (ref "R47") (pin "1") (pinfunction "1_1") (pintype "input"))
    )
    (net (code "131") (name "Net-(LED4-A)") (class "Default")
      (node (ref "LED4") (pin "1") (pinfunction "A_1") (pintype "unspecified"))
      (node (ref "R17") (pin "1") (pinfunction "1_1") (pintype "input"))
    )
    (net (code "132") (name "Net-(LED5-A)") (class "Default")
      (node (ref "LED5") (pin "1") (pinfunction "A_1") (pintype "unspecified"))
      (node (ref "R19") (pin "1") (pinfunction "1_1") (pintype "input"))
    )
    (net (code "133") (name "Net-(LED6-A)") (class "Default")
      (node (ref "LED6") (pin "1") (pinfunction "A_1") (pintype "unspecified"))
      (node (ref "R18") (pin "1") (pinfunction "1_1") (pintype "input"))
    )
    (net (code "134") (name "Net-(LED7-A)") (class "Default")
      (node (ref "LED7") (pin "1") (pinfunction "A_1") (pintype "unspecified"))
      (node (ref "R21") (pin "1") (pinfunction "1_1") (pintype "input"))
    )
    (net (code "135") (name "Net-(LED8-A)") (class "Default")
      (node (ref "LED8") (pin "1") (pinfunction "A_1") (pintype "unspecified"))
      (node (ref "R20") (pin "1") (pinfunction "1_1") (pintype "input"))
    )
    (net (code "136") (name "Net-(LED9-A)") (class "Default")
      (node (ref "LED9") (pin "2") (pinfunction "A_2") (pintype "unspecified"))
      (node (ref "R30") (pin "1") (pinfunction "1_1") (pintype "input"))
    )
    (net (code "137") (name "Net-(LED10-A)") (class "Default")
      (node (ref "LED10") (pin "2") (pinfunction "A_2") (pintype "unspecified"))
      (node (ref "R29") (pin "1") (pinfunction "1_1") (pintype "input"))
    )
    (net (code "138") (name "Net-(LED11-A)") (class "Default")
      (node (ref "LED11") (pin "1") (pinfunction "A_1") (pintype "unspecified"))
      (node (ref "R23") (pin "1") (pinfunction "1_1") (pintype "input"))
    )
    (net (code "139") (name "Net-(LED12-A)") (class "Default")
      (node (ref "LED12") (pin "1") (pinfunction "A_1") (pintype "unspecified"))
      (node (ref "R22") (pin "1") (pinfunction "1_1") (pintype "input"))
    )
    (net (code "140") (name "Net-(LED13-A)") (class "Default")
      (node (ref "LED13") (pin "1") (pinfunction "A_1") (pintype "unspecified"))
      (node (ref "R48") (pin "2") (pinfunction "2_2") (pintype "input"))
    )
    (net (code "141") (name "Net-(LED14-A)") (class "Default")
      (node (ref "LED14") (pin "1") (pinfunction "A_1") (pintype "unspecified"))
      (node (ref "R56") (pin "2") (pinfunction "2_2") (pintype "input"))
    )
    (net (code "142") (name "Net-(P4-Pad1)") (class "Default")
      (node (ref "P4") (pin "1") (pinfunction "1_1") (pintype "unspecified"))
      (node (ref "USB_C1") (pin "A4") (pinfunction "VBUS_A4") (pintype "unspecified"))
      (node (ref "USB_C1") (pin "A9") (pinfunction "VBUS_A9") (pintype "unspecified"))
      (node (ref "USB_C1") (pin "B4") (pinfunction "VBUS_B4") (pintype "unspecified"))
      (node (ref "USB_C1") (pin "B9") (pinfunction "VBUS_B9") (pintype "unspecified"))
    )
    (net (code "143") (name "Net-(P9-Pad2)") (class "Default")
      (node (ref "P9") (pin "2") (pinfunction "2_2") (pintype "unspecified"))
      (node (ref "U13") (pin "1") (pinfunction "1_1") (pintype "unspecified"))
    )
    (net (code "144") (name "Net-(U1-A)") (class "Default")
      (node (ref "R27") (pin "1") (pinfunction "1_1") (pintype "input"))
      (node (ref "U1") (pin "15") (pinfunction "A_15") (pintype "passive"))
    )
    (net (code "145") (name "Net-(U4-VU)") (class "Default")
      (node (ref "P9") (pin "1") (pinfunction "1_1") (pintype "unspecified"))
      (node (ref "U4") (pin "24") (pinfunction "VU_24") (pintype "unspecified"))
    )
    (net (code "146") (name "Net-(USB_C1-CC1)") (class "Default")
      (node (ref "R37") (pin "2") (pinfunction "2_2") (pintype "input"))
      (node (ref "USB_C1") (pin "A5") (pinfunction "CC1_A5") (pintype "unspecified"))
    )
    (net (code "147") (name "Net-(USB_C1-CC2)") (class "Default")
      (node (ref "R28") (pin "2") (pinfunction "2_2") (pintype "input"))
      (node (ref "USB_C1") (pin "B5") (pinfunction "CC2_B5") (pintype "unspecified"))
    )
    (net (code "148") (name "OE") (class "Default")
      (node (ref "J1") (pin "8") (pinfunction "8_8") (pintype "bidirectional"))
      (node (ref "U10") (pin "18") (pinfunction "B4_18") (pintype "unspecified"))
    )
    (net (code "149") (name "OE_STM") (class "Default")
      (node (ref "DEV1") (pin "24") (pinfunction "OSC/PC-15_24") (pintype "unspecified"))
      (node (ref "R58") (pin "2") (pinfunction "2_2") (pintype "input"))
      (node (ref "U10") (pin "6") (pinfunction "A4_6") (pintype "unspecified"))
    )
    (net (code "150") (name "OE_Translator") (class "Default")
      (node (ref "H7") (pin "2") (pinfunction "2_2") (pintype "input"))
      (node (ref "U10") (pin "22") (pinfunction "OE#_22") (pintype "unspecified"))
      (node (ref "U12") (pin "22") (pinfunction "OE#_22") (pintype "unspecified"))
      (node (ref "U8") (pin "22") (pinfunction "OE#_22") (pintype "unspecified"))
    )
    (net (code "151") (name "POT1") (class "Default")
      (node (ref "HR_B1") (pin "10") (pinfunction "10_10") (pintype "unspecified"))
      (node (ref "P6") (pin "1") (pinfunction "1_1") (pintype "input"))
      (node (ref "POT1") (pin "2") (pinfunction "2_2") (pintype "input"))
      (node (ref "U4") (pin "15") (pinfunction "15_Analog_15") (pintype "unspecified"))
    )
    (net (code "152") (name "POT2") (class "Default")
      (node (ref "HR_B1") (pin "9") (pinfunction "9_9") (pintype "unspecified"))
      (node (ref "P7") (pin "1") (pinfunction "1_1") (pintype "input"))
      (node (ref "POT2") (pin "2") (pinfunction "2_2") (pintype "input"))
      (node (ref "U4") (pin "16") (pinfunction "16_Analog_16") (pintype "unspecified"))
    )
    (net (code "153") (name "PRTA_1") (class "Default")
      (node (ref "HR_B2") (pin "20") (pinfunction "20_20") (pintype "unspecified"))
      (node (ref "JP1") (pin "8") (pinfunction "8_8") (pintype "unspecified"))
      (node (ref "JP10") (pin "8") (pinfunction "8_8") (pintype "unspecified"))
      (node (ref "U4") (pin "29") (pinfunction "29_29") (pintype "unspecified"))
    )
    (net (code "154") (name "PRTA_2") (class "Default")
      (node (ref "HR_B2") (pin "19") (pinfunction "19_19") (pintype "unspecified"))
      (node (ref "JP1") (pin "7") (pinfunction "7_7") (pintype "unspecified"))
      (node (ref "JP10") (pin "7") (pinfunction "7_7") (pintype "unspecified"))
      (node (ref "U4") (pin "30") (pinfunction "30_30") (pintype "unspecified"))
    )
    (net (code "155") (name "PRTA_3") (class "Default")
      (node (ref "HR_B2") (pin "18") (pinfunction "18_18") (pintype "unspecified"))
      (node (ref "JP1") (pin "6") (pinfunction "6_6") (pintype "unspecified"))
      (node (ref "JP10") (pin "6") (pinfunction "6_6") (pintype "unspecified"))
      (node (ref "U4") (pin "31") (pinfunction "31_31") (pintype "unspecified"))
    )
    (net (code "156") (name "PRTA_4") (class "Default")
      (node (ref "HR_B2") (pin "17") (pinfunction "17_17") (pintype "unspecified"))
      (node (ref "JP1") (pin "5") (pinfunction "5_5") (pintype "unspecified"))
      (node (ref "JP10") (pin "5") (pinfunction "5_5") (pintype "unspecified"))
      (node (ref "U4") (pin "32") (pinfunction "32_32") (pintype "unspecified"))
    )
    (net (code "157") (name "PRTA_5") (class "Default")
      (node (ref "HR_B2") (pin "16") (pinfunction "16_16") (pintype "unspecified"))
      (node (ref "JP1") (pin "4") (pinfunction "4_4") (pintype "unspecified"))
      (node (ref "JP10") (pin "4") (pinfunction "4_4") (pintype "unspecified"))
      (node (ref "U4") (pin "33") (pinfunction "33_33") (pintype "unspecified"))
    )
    (net (code "158") (name "PRTA_6") (class "Default")
      (node (ref "HR_B2") (pin "15") (pinfunction "15_15") (pintype "unspecified"))
      (node (ref "JP1") (pin "3") (pinfunction "3_3") (pintype "unspecified"))
      (node (ref "JP10") (pin "3") (pinfunction "3_3") (pintype "unspecified"))
      (node (ref "U4") (pin "34") (pinfunction "34_34") (pintype "unspecified"))
    )
    (net (code "159") (name "PRTA_7") (class "Default")
      (node (ref "HR_B2") (pin "14") (pinfunction "14_14") (pintype "unspecified"))
      (node (ref "JP1") (pin "2") (pinfunction "2_2") (pintype "unspecified"))
      (node (ref "JP10") (pin "2") (pinfunction "2_2") (pintype "unspecified"))
      (node (ref "U4") (pin "35") (pinfunction "35_35") (pintype "unspecified"))
    )
    (net (code "160") (name "PRTA_8") (class "Default")
      (node (ref "HR_B2") (pin "13") (pinfunction "13_13") (pintype "unspecified"))
      (node (ref "JP1") (pin "1") (pinfunction "1_1") (pintype "unspecified"))
      (node (ref "JP10") (pin "1") (pinfunction "1_1") (pintype "unspecified"))
      (node (ref "U4") (pin "36") (pinfunction "36_36") (pintype "unspecified"))
    )
    (net (code "161") (name "PRTB_1") (class "Default")
      (node (ref "HR_B2") (pin "12") (pinfunction "12_12") (pintype "unspecified"))
      (node (ref "JP6") (pin "8") (pinfunction "8_8") (pintype "unspecified"))
      (node (ref "JP9") (pin "8") (pinfunction "8_8") (pintype "unspecified"))
      (node (ref "U4") (pin "37") (pinfunction "37_37") (pintype "unspecified"))
    )
    (net (code "162") (name "PRTB_2") (class "Default")
      (node (ref "HR_B2") (pin "11") (pinfunction "11_11") (pintype "unspecified"))
      (node (ref "JP6") (pin "7") (pinfunction "7_7") (pintype "unspecified"))
      (node (ref "JP9") (pin "7") (pinfunction "7_7") (pintype "unspecified"))
      (node (ref "U4") (pin "38") (pinfunction "38_38") (pintype "unspecified"))
    )
    (net (code "163") (name "PRTB_3") (class "Default")
      (node (ref "HR_B2") (pin "10") (pinfunction "10_10") (pintype "unspecified"))
      (node (ref "JP6") (pin "6") (pinfunction "6_6") (pintype "unspecified"))
      (node (ref "JP9") (pin "6") (pinfunction "6_6") (pintype "unspecified"))
      (node (ref "U4") (pin "39") (pinfunction "39_39") (pintype "unspecified"))
    )
    (net (code "164") (name "PRTB_4") (class "Default")
      (node (ref "HR_B2") (pin "9") (pinfunction "9_9") (pintype "unspecified"))
      (node (ref "JP6") (pin "5") (pinfunction "5_5") (pintype "unspecified"))
      (node (ref "JP9") (pin "5") (pinfunction "5_5") (pintype "unspecified"))
      (node (ref "U4") (pin "40") (pinfunction "40_40") (pintype "unspecified"))
    )
    (net (code "165") (name "PRTB_5") (class "Default")
      (node (ref "HR_B2") (pin "8") (pinfunction "8_8") (pintype "unspecified"))
      (node (ref "JP6") (pin "4") (pinfunction "4_4") (pintype "unspecified"))
      (node (ref "JP9") (pin "4") (pinfunction "4_4") (pintype "unspecified"))
      (node (ref "U4") (pin "41") (pinfunction "41_41") (pintype "unspecified"))
    )
    (net (code "166") (name "PRTB_6") (class "Default")
      (node (ref "HR_B2") (pin "7") (pinfunction "7_7") (pintype "unspecified"))
      (node (ref "JP6") (pin "3") (pinfunction "3_3") (pintype "unspecified"))
      (node (ref "JP9") (pin "3") (pinfunction "3_3") (pintype "unspecified"))
      (node (ref "U4") (pin "42") (pinfunction "42_42") (pintype "unspecified"))
    )
    (net (code "167") (name "PRTB_7") (class "Default")
      (node (ref "HR_B2") (pin "6") (pinfunction "6_6") (pintype "unspecified"))
      (node (ref "JP6") (pin "2") (pinfunction "2_2") (pintype "unspecified"))
      (node (ref "JP9") (pin "2") (pinfunction "2_2") (pintype "unspecified"))
      (node (ref "U4") (pin "43") (pinfunction "43_43") (pintype "unspecified"))
    )
    (net (code "168") (name "PRTB_8") (class "Default")
      (node (ref "HR_B2") (pin "5") (pinfunction "5_5") (pintype "unspecified"))
      (node (ref "JP6") (pin "1") (pinfunction "1_1") (pintype "unspecified"))
      (node (ref "JP9") (pin "1") (pinfunction "1_1") (pintype "unspecified"))
      (node (ref "U4") (pin "44") (pinfunction "44_44") (pintype "unspecified"))
    )
    (net (code "169") (name "PWMBuzzer") (class "Default")
      (node (ref "BUZZER1") (pin "1") (pinfunction "+_1") (pintype "unspecified"))
      (node (ref "U3") (pin "1") (pinfunction "1_1") (pintype "unspecified"))
    )
    (net (code "170") (name "PWMLED1") (class "Default")
      (node (ref "R30") (pin "2") (pinfunction "2_2") (pintype "input"))
      (node (ref "U3") (pin "3") (pinfunction "3_3") (pintype "unspecified"))
    )
    (net (code "171") (name "Rx") (class "Default")
      (node (ref "CH1G") (pin "3") (pinfunction "RXD_3") (pintype "unspecified"))
      (node (ref "HR_B2") (pin "1") (pinfunction "1_1") (pintype "unspecified"))
      (node (ref "LED1") (pin "2") (pinfunction "K_2") (pintype "unspecified"))
      (node (ref "U4") (pin "48") (pinfunction "48_48") (pintype "unspecified"))
    )
    (net (code "172") (name "SCLK") (class "Default")
      (node (ref "JP8") (pin "8") (pinfunction "8_8") (pintype "unspecified"))
      (node (ref "U7") (pin "4") (pinfunction "SCLK_4") (pintype "unspecified"))
      (node (ref "U9") (pin "2") (pinfunction "CLK_2") (pintype "unspecified"))
    )
    (net (code "173") (name "SDA") (class "Default")
      (node (ref "JP8") (pin "7") (pinfunction "7_7") (pintype "unspecified"))
      (node (ref "U7") (pin "2") (pinfunction "SDA_2") (pintype "unspecified"))
    )
    (net (code "174") (name "SEG_0") (class "Default")
      (node (ref "R55") (pin "1") (pinfunction "1_1") (pintype "input"))
      (node (ref "SHIFT_REG1") (pin "15") (pinfunction "Q0_15") (pintype "unspecified"))
    )
    (net (code "175") (name "SEG_1") (class "Default")
      (node (ref "R54") (pin "1") (pinfunction "1_1") (pintype "input"))
      (node (ref "SHIFT_REG1") (pin "1") (pinfunction "Q1_1") (pintype "unspecified"))
    )
    (net (code "176") (name "SEG_2") (class "Default")
      (node (ref "R53") (pin "1") (pinfunction "1_1") (pintype "input"))
      (node (ref "SHIFT_REG1") (pin "2") (pinfunction "Q2_2") (pintype "unspecified"))
    )
    (net (code "177") (name "SEG_3") (class "Default")
      (node (ref "R52") (pin "1") (pinfunction "1_1") (pintype "input"))
      (node (ref "SHIFT_REG1") (pin "3") (pinfunction "Q3_3") (pintype "unspecified"))
    )
    (net (code "178") (name "SEG_4") (class "Default")
      (node (ref "R51") (pin "1") (pinfunction "1_1") (pintype "input"))
      (node (ref "SHIFT_REG1") (pin "4") (pinfunction "Q4_4") (pintype "unspecified"))
    )
    (net (code "179") (name "SEG_5") (class "Default")
      (node (ref "R44") (pin "1") (pinfunction "1_1") (pintype "input"))
      (node (ref "SHIFT_REG1") (pin "5") (pinfunction "Q5_5") (pintype "unspecified"))
    )
    (net (code "180") (name "SEG_6") (class "Default")
      (node (ref "R43") (pin "1") (pinfunction "1_1") (pintype "input"))
      (node (ref "SHIFT_REG1") (pin "6") (pinfunction "Q6_6") (pintype "unspecified"))
    )
    (net (code "181") (name "SEG_7") (class "Default")
      (node (ref "R42") (pin "1") (pinfunction "1_1") (pintype "input"))
      (node (ref "SHIFT_REG1") (pin "7") (pinfunction "Q7_7") (pintype "unspecified"))
    )
    (net (code "182") (name "SHCP") (class "Default")
      (node (ref "JP8") (pin "1") (pinfunction "1_1") (pintype "unspecified"))
      (node (ref "R46") (pin "2") (pinfunction "2_2") (pintype "input"))
      (node (ref "SHIFT_REG1") (pin "11") (pinfunction "SHCP_11") (pintype "unspecified"))
    )
    (net (code "183") (name "STCP") (class "Default")
      (node (ref "JP8") (pin "2") (pinfunction "2_2") (pintype "unspecified"))
      (node (ref "R45") (pin "2") (pinfunction "2_2") (pintype "input"))
      (node (ref "SHIFT_REG1") (pin "12") (pinfunction "STCP_12") (pintype "unspecified"))
    )
    (net (code "184") (name "STMP1") (class "Default")
      (node (ref "DEV1") (pin "4") (pinfunction "PB15/SD_CK_4") (pintype "unspecified"))
    )
    (net (code "185") (name "STMP2") (class "Default")
      (node (ref "DEV1") (pin "3") (pinfunction "PB-14/PWM_3") (pintype "unspecified"))
    )
    (net (code "186") (name "SW1") (class "Default")
      (node (ref "C24") (pin "2") (pinfunction "2_2") (pintype "input"))
      (node (ref "R16") (pin "2") (pinfunction "2_2") (pintype "input"))
      (node (ref "SW1") (pin "3") (pinfunction "C_3") (pintype "unspecified"))
      (node (ref "SW1") (pin "4") (pinfunction "D_4") (pintype "unspecified"))
    )
    (net (code "187") (name "SW2") (class "Default")
      (node (ref "C23") (pin "2") (pinfunction "2_2") (pintype "input"))
      (node (ref "R15") (pin "2") (pinfunction "2_2") (pintype "input"))
      (node (ref "SW2") (pin "3") (pinfunction "C_3") (pintype "unspecified"))
      (node (ref "SW2") (pin "4") (pinfunction "D_4") (pintype "unspecified"))
    )
    (net (code "188") (name "SW3") (class "Default")
      (node (ref "C22") (pin "2") (pinfunction "2_2") (pintype "input"))
      (node (ref "R14") (pin "2") (pinfunction "2_2") (pintype "input"))
      (node (ref "SW3") (pin "3") (pinfunction "C_3") (pintype "unspecified"))
      (node (ref "SW3") (pin "4") (pinfunction "D_4") (pintype "unspecified"))
    )
    (net (code "189") (name "SW4") (class "Default")
      (node (ref "C21") (pin "2") (pinfunction "2_2") (pintype "input"))
      (node (ref "R13") (pin "2") (pinfunction "2_2") (pintype "input"))
      (node (ref "SW4") (pin "3") (pinfunction "C_3") (pintype "unspecified"))
      (node (ref "SW4") (pin "4") (pinfunction "D_4") (pintype "unspecified"))
    )
    (net (code "190") (name "SW5") (class "Default")
      (node (ref "C16") (pin "2") (pinfunction "2_2") (pintype "input"))
      (node (ref "R9") (pin "2") (pinfunction "2_2") (pintype "input"))
      (node (ref "SW5") (pin "3") (pinfunction "C_3") (pintype "unspecified"))
      (node (ref "SW5") (pin "4") (pinfunction "D_4") (pintype "unspecified"))
    )
    (net (code "191") (name "SW6") (class "Default")
      (node (ref "C17") (pin "2") (pinfunction "2_2") (pintype "input"))
      (node (ref "R10") (pin "2") (pinfunction "2_2") (pintype "input"))
      (node (ref "SW6") (pin "3") (pinfunction "C_3") (pintype "unspecified"))
      (node (ref "SW6") (pin "4") (pinfunction "D_4") (pintype "unspecified"))
    )
    (net (code "192") (name "SW7") (class "Default")
      (node (ref "C19") (pin "2") (pinfunction "2_2") (pintype "input"))
      (node (ref "R11") (pin "2") (pinfunction "2_2") (pintype "input"))
      (node (ref "SW7") (pin "3") (pinfunction "C_3") (pintype "unspecified"))
      (node (ref "SW7") (pin "4") (pinfunction "D_4") (pintype "unspecified"))
    )
    (net (code "193") (name "SW8") (class "Default")
      (node (ref "C20") (pin "2") (pinfunction "2_2") (pintype "input"))
      (node (ref "R12") (pin "2") (pinfunction "2_2") (pintype "input"))
      (node (ref "SW8") (pin "3") (pinfunction "C_3") (pintype "unspecified"))
      (node (ref "SW8") (pin "4") (pinfunction "D_4") (pintype "unspecified"))
    )
    (net (code "194") (name "Sw1") (class "Default")
      (node (ref "JP2") (pin "8") (pinfunction "8_8") (pintype "unspecified"))
    )
    (net (code "195") (name "Sw2") (class "Default")
      (node (ref "JP2") (pin "7") (pinfunction "7_7") (pintype "unspecified"))
    )
    (net (code "196") (name "Sw3") (class "Default")
      (node (ref "JP2") (pin "6") (pinfunction "6_6") (pintype "unspecified"))
    )
    (net (code "197") (name "Sw4") (class "Default")
      (node (ref "JP2") (pin "5") (pinfunction "5_5") (pintype "unspecified"))
    )
    (net (code "198") (name "Sw5") (class "Default")
      (node (ref "JP2") (pin "4") (pinfunction "4_4") (pintype "unspecified"))
    )
    (net (code "199") (name "Sw6") (class "Default")
      (node (ref "JP2") (pin "3") (pinfunction "3_3") (pintype "unspecified"))
    )
    (net (code "200") (name "Sw7") (class "Default")
      (node (ref "JP2") (pin "2") (pinfunction "2_2") (pintype "unspecified"))
    )
    (net (code "201") (name "Sw8") (class "Default")
      (node (ref "JP2") (pin "1") (pinfunction "1_1") (pintype "unspecified"))
    )
    (net (code "202") (name "TCA") (class "Default")
      (node (ref "HR_B2") (pin "4") (pinfunction "4_4") (pintype "unspecified"))
      (node (ref "U3") (pin "2") (pinfunction "2_2") (pintype "unspecified"))
      (node (ref "U4") (pin "45") (pinfunction "45_45") (pintype "unspecified"))
    )
    (net (code "203") (name "TCB") (class "Default")
      (node (ref "HR_B2") (pin "3") (pinfunction "3_3") (pintype "unspecified"))
      (node (ref "P13") (pin "1") (pinfunction "1_1") (pintype "input"))
      (node (ref "R29") (pin "2") (pinfunction "2_2") (pintype "input"))
      (node (ref "U4") (pin "46") (pinfunction "46_46") (pintype "unspecified"))
    )
    (net (code "204") (name "Tx") (class "Default")
      (node (ref "CH1G") (pin "2") (pinfunction "TXD_2") (pintype "unspecified"))
      (node (ref "HR_B2") (pin "2") (pinfunction "2_2") (pintype "unspecified"))
      (node (ref "LED2") (pin "2") (pinfunction "K_2") (pintype "unspecified"))
      (node (ref "U4") (pin "47") (pinfunction "47_47") (pintype "unspecified"))
    )
    (net (code "205") (name "USBC") (class "Default")
      (node (ref "C25") (pin "1") (pinfunction "1_1") (pintype "input"))
      (node (ref "C26") (pin "2") (pinfunction "2_2") (pintype "unspecified"))
      (node (ref "D2") (pin "1") (pinfunction "C_1") (pintype "unspecified"))
      (node (ref "P4") (pin "2") (pinfunction "2_2") (pintype "unspecified"))
      (node (ref "U5") (pin "2") (pinfunction "A_2") (pintype "unspecified"))
    )
    (net (code "206") (name "USB_D+") (class "Default")
      (node (ref "CH1G") (pin "5") (pinfunction "UD+_5") (pintype "unspecified"))
      (node (ref "ESD1") (pin "3") (pinfunction "3_3") (pintype "unspecified"))
      (node (ref "USB_C1") (pin "A6") (pinfunction "DP1_A6") (pintype "unspecified"))
      (node (ref "USB_C1") (pin "B6") (pinfunction "DP2_B6") (pintype "unspecified"))
    )
    (net (code "207") (name "USB_D-") (class "Default")
      (node (ref "CH1G") (pin "6") (pinfunction "UD-_6") (pintype "unspecified"))
      (node (ref "ESD1") (pin "2") (pinfunction "2_2") (pintype "unspecified"))
      (node (ref "USB_C1") (pin "A7") (pinfunction "DN1_A7") (pintype "unspecified"))
      (node (ref "USB_C1") (pin "B7") (pinfunction "DN2_B7") (pintype "unspecified"))
    )
    (net (code "208") (name "USR_BTN") (class "Default")
      (node (ref "C3") (pin "2") (pinfunction "2_2") (pintype "input"))
      (node (ref "HR_B2") (pin "21") (pinfunction "21_21") (pintype "unspecified"))
      (node (ref "R24") (pin "2") (pinfunction "2_2") (pintype "input"))
      (node (ref "U4") (pin "28") (pinfunction "28_28") (pintype "unspecified"))
      (node (ref "USR_BTN") (pin "3") (pinfunction "C_3") (pintype "unspecified"))
      (node (ref "USR_BTN") (pin "4") (pinfunction "D_4") (pintype "unspecified"))
    )
    (net (code "209") (name "VCC") (class "Default")
      (node (ref "3.3V_REG1") (pin "2") (pinfunction "VOUT_2") (pintype "unspecified"))
      (node (ref "C1") (pin "2") (pinfunction "2_2") (pintype "input"))
      (node (ref "C10") (pin "2") (pinfunction "2_2") (pintype "unspecified"))
      (node (ref "C13") (pin "2") (pinfunction "2_2") (pintype "unspecified"))
      (node (ref "C14") (pin "2") (pinfunction "2_2") (pintype "unspecified"))
      (node (ref "C15") (pin "2") (pinfunction "2_2") (pintype "unspecified"))
      (node (ref "C18") (pin "2") (pinfunction "2_2") (pintype "input"))
      (node (ref "C9") (pin "2") (pinfunction "2_2") (pintype "unspecified"))
      (node (ref "CH1G") (pin "16") (pinfunction "VCC_16") (pintype "unspecified"))
      (node (ref "CH1G") (pin "4") (pinfunction "V3_4") (pintype "unspecified"))
      (node (ref "H4") (pin "1") (pinfunction "1_1") (pintype "unspecified"))
      (node (ref "H4") (pin "2") (pinfunction "2_2") (pintype "unspecified"))
      (node (ref "H4") (pin "3") (pinfunction "3_3") (pintype "unspecified"))
      (node (ref "H4") (pin "4") (pinfunction "4_4") (pintype "unspecified"))
      (node (ref "H4") (pin "45") (pinfunction "45_45") (pintype "unspecified"))
      (node (ref "H4") (pin "46") (pinfunction "46_46") (pintype "unspecified"))
      (node (ref "H4") (pin "47") (pinfunction "47_47") (pintype "unspecified"))
      (node (ref "H4") (pin "48") (pinfunction "48_48") (pintype "unspecified"))
      (node (ref "H5") (pin "2") (pinfunction "2_2") (pintype "unspecified"))
      (node (ref "H5") (pin "4") (pinfunction "4_4") (pintype "unspecified"))
      (node (ref "H5") (pin "46") (pinfunction "46_46") (pintype "unspecified"))
      (node (ref "H5") (pin "48") (pinfunction "48_48") (pintype "unspecified"))
      (node (ref "H7") (pin "3") (pinfunction "3_3") (pintype "input"))
      (node (ref "LCD1") (pin "2") (pinfunction "VCC_2") (pintype "unspecified"))
      (node (ref "MCLR") (pin "1") (pinfunction "A_1") (pintype "unspecified"))
      (node (ref "MCLR") (pin "2") (pinfunction "B_2") (pintype "unspecified"))
      (node (ref "P11") (pin "1") (pinfunction "1_1") (pintype "input"))
      (node (ref "POT1") (pin "3") (pinfunction "3_3") (pintype "input"))
      (node (ref "POT2") (pin "3") (pinfunction "3_3") (pintype "input"))
      (node (ref "R25") (pin "3") (pinfunction "3_3") (pintype "unspecified"))
      (node (ref "R26") (pin "2") (pinfunction "2_2") (pintype "input"))
      (node (ref "R27") (pin "2") (pinfunction "2_2") (pintype "input"))
      (node (ref "R49") (pin "2") (pinfunction "2_2") (pintype "input"))
      (node (ref "R50") (pin "2") (pinfunction "2_2") (pintype "input"))
      (node (ref "R61") (pin "1") (pinfunction "1_1") (pintype "input"))
      (node (ref "SHIFT_REG1") (pin "10") (pinfunction "MR#_10") (pintype "unspecified"))
      (node (ref "SHIFT_REG1") (pin "16") (pinfunction "VCC_16") (pintype "unspecified"))
      (node (ref "SW1") (pin "1") (pinfunction "A_1") (pintype "unspecified"))
      (node (ref "SW1") (pin "2") (pinfunction "B_2") (pintype "unspecified"))
      (node (ref "SW11") (pin "1") (pinfunction "1_1") (pintype "unspecified"))
      (node (ref "SW11") (pin "2") (pinfunction "2_2") (pintype "unspecified"))
      (node (ref "SW11") (pin "3") (pinfunction "3_3") (pintype "unspecified"))
      (node (ref "SW11") (pin "4") (pinfunction "4_4") (pintype "unspecified"))
      (node (ref "SW11") (pin "5") (pinfunction "5_5") (pintype "unspecified"))
      (node (ref "SW11") (pin "6") (pinfunction "6_6") (pintype "unspecified"))
      (node (ref "SW11") (pin "7") (pinfunction "7_7") (pintype "unspecified"))
      (node (ref "SW11") (pin "8") (pinfunction "8_8") (pintype "unspecified"))
      (node (ref "SW2") (pin "1") (pinfunction "A_1") (pintype "unspecified"))
      (node (ref "SW2") (pin "2") (pinfunction "B_2") (pintype "unspecified"))
      (node (ref "SW3") (pin "1") (pinfunction "A_1") (pintype "unspecified"))
      (node (ref "SW3") (pin "2") (pinfunction "B_2") (pintype "unspecified"))
      (node (ref "SW4") (pin "1") (pinfunction "A_1") (pintype "unspecified"))
      (node (ref "SW4") (pin "2") (pinfunction "B_2") (pintype "unspecified"))
      (node (ref "SW5") (pin "1") (pinfunction "A_1") (pintype "unspecified"))
      (node (ref "SW5") (pin "2") (pinfunction "B_2") (pintype "unspecified"))
      (node (ref "SW6") (pin "1") (pinfunction "A_1") (pintype "unspecified"))
      (node (ref "SW6") (pin "2") (pinfunction "B_2") (pintype "unspecified"))
      (node (ref "SW7") (pin "1") (pinfunction "A_1") (pintype "unspecified"))
      (node (ref "SW7") (pin "2") (pinfunction "B_2") (pintype "unspecified"))
      (node (ref "SW8") (pin "1") (pinfunction "A_1") (pintype "unspecified"))
      (node (ref "SW8") (pin "2") (pinfunction "B_2") (pintype "unspecified"))
      (node (ref "U1") (pin "2") (pinfunction "VDD_2") (pintype "passive"))
      (node (ref "U10") (pin "1") (pinfunction "VCCA_1") (pintype "unspecified"))
      (node (ref "U10") (pin "2") (pinfunction "DIR_2") (pintype "unspecified"))
      (node (ref "U12") (pin "1") (pinfunction "VCCA_1") (pintype "unspecified"))
      (node (ref "U7") (pin "5") (pinfunction "VDD_5") (pintype "unspecified"))
      (node (ref "U8") (pin "1") (pinfunction "VCCA_1") (pintype "unspecified"))
      (node (ref "U8") (pin "2") (pinfunction "DIR_2") (pintype "unspecified"))
      (node (ref "U9") (pin "8") (pinfunction "VCC_8") (pintype "unspecified"))
      (node (ref "USR_BTN") (pin "1") (pinfunction "A_1") (pintype "unspecified"))
      (node (ref "USR_BTN") (pin "2") (pinfunction "B_2") (pintype "unspecified"))
    )
    (net (code "210") (name "WE") (class "Default")
      (node (ref "J1") (pin "13") (pinfunction "13_13") (pintype "bidirectional"))
      (node (ref "U10") (pin "14") (pinfunction "B8_14") (pintype "unspecified"))
    )
    (net (code "211") (name "WE_STM") (class "Default")
      (node (ref "DEV1") (pin "23") (pinfunction "OSC/PC-14_23") (pintype "unspecified"))
      (node (ref "R61") (pin "2") (pinfunction "2_2") (pintype "input"))
      (node (ref "U10") (pin "10") (pinfunction "A8_10") (pintype "unspecified"))
    )
    (net (code "212") (name "unconnected-(CH1G-CTS#-Pad9)") (class "Default")
      (node (ref "CH1G") (pin "9") (pinfunction "CTS#_9") (pintype "unspecified"))
    )
    (net (code "213") (name "unconnected-(CH1G-DCD#-Pad12)") (class "Default")
      (node (ref "CH1G") (pin "12") (pinfunction "DCD#_12") (pintype "unspecified"))
    )
    (net (code "214") (name "unconnected-(CH1G-DSR#-Pad10)") (class "Default")
      (node (ref "CH1G") (pin "10") (pinfunction "DSR#_10") (pintype "unspecified"))
    )
    (net (code "215") (name "unconnected-(CH1G-DTR#-Pad13)") (class "Default")
      (node (ref "CH1G") (pin "13") (pinfunction "DTR#_13") (pintype "unspecified"))
    )
    (net (code "216") (name "unconnected-(CH1G-R232-Pad15)") (class "Default")
      (node (ref "CH1G") (pin "15") (pinfunction "R232_15") (pintype "unspecified"))
    )
    (net (code "217") (name "unconnected-(CH1G-RI#-Pad11)") (class "Default")
      (node (ref "CH1G") (pin "11") (pinfunction "RI#_11") (pintype "unspecified"))
    )
    (net (code "218") (name "unconnected-(CH1G-RTS#-Pad14)") (class "Default")
      (node (ref "CH1G") (pin "14") (pinfunction "RTS#_14") (pintype "unspecified"))
    )
    (net (code "219") (name "unconnected-(DEV1-+3.3V-Pad20)") (class "Default")
      (node (ref "DEV1") (pin "20") (pinfunction "+3.3V_20") (pintype "unspecified"))
    )
    (net (code "220") (name "unconnected-(DEV1-+3.3V-Pad38)") (class "Default")
      (node (ref "DEV1") (pin "38") (pinfunction "+3.3V_38") (pintype "unspecified"))
    )
    (net (code "221") (name "unconnected-(DEV1-+5V-Pad18)") (class "Default")
      (node (ref "DEV1") (pin "18") (pinfunction "+5V_18") (pintype "unspecified"))
    )
    (net (code "222") (name "unconnected-(DEV1-GND-Pad19)") (class "Default")
      (node (ref "DEV1") (pin "19") (pinfunction "GND_19") (pintype "unspecified"))
    )
    (net (code "223") (name "unconnected-(DEV1-LED{slash}PC-13-Pad22)") (class "Default")
      (node (ref "DEV1") (pin "22") (pinfunction "LED/PC-13_22") (pintype "unspecified+no_connect"))
    )
    (net (code "224") (name "unconnected-(DEV1-NRST-Pad25)") (class "Default")
      (node (ref "DEV1") (pin "25") (pinfunction "NRST_25") (pintype "unspecified"))
    )
    (net (code "225") (name "unconnected-(DEV1-PA-11{slash}USB{slash}TX6-Pad8)") (class "Default")
      (node (ref "DEV1") (pin "8") (pinfunction "PA-11/USB/TX6_8") (pintype "unspecified"))
    )
    (net (code "226") (name "unconnected-(DEV1-PA-12{slash}USB{slash}RX6-Pad9)") (class "Default")
      (node (ref "DEV1") (pin "9") (pinfunction "PA-12/USB/RX6_9") (pintype "unspecified"))
    )
    (net (code "227") (name "unconnected-(DEV1-PA-15{slash}PWM-Pad10)") (class "Default")
      (node (ref "DEV1") (pin "10") (pinfunction "PA-15/PWM_10") (pintype "unspecified"))
    )
    (net (code "228") (name "unconnected-(DEV1-PB-9{slash}SDA1-Pad17)") (class "Default")
      (node (ref "DEV1") (pin "17") (pinfunction "PB-9/SDA1_17") (pintype "unspecified"))
    )
    (net (code "229") (name "unconnected-(DEV1-VBAT-Pad21)") (class "Default")
      (node (ref "DEV1") (pin "21") (pinfunction "VBAT_21") (pintype "unspecified"))
    )
    (net (code "230") (name "unconnected-(J1-Pad12)") (class "Default")
      (node (ref "J1") (pin "12") (pinfunction "12_12") (pintype "bidirectional"))
    )
    (net (code "231") (name "unconnected-(J1-Pad15)") (class "Default")
      (node (ref "J1") (pin "15") (pinfunction "15_15") (pintype "bidirectional"))
    )
    (net (code "232") (name "unconnected-(J1-PadMH1)") (class "Default")
      (node (ref "J1") (pin "MH1") (pinfunction "MH1_MH1") (pintype "bidirectional+no_connect"))
    )
    (net (code "233") (name "unconnected-(J1-PadMH2)") (class "Default")
      (node (ref "J1") (pin "MH2") (pinfunction "MH2_MH2") (pintype "bidirectional+no_connect"))
    )
    (net (code "234") (name "unconnected-(LCD1-DB0-Pad7)") (class "Default")
      (node (ref "LCD1") (pin "7") (pinfunction "DB0_7") (pintype "unspecified+no_connect"))
    )
    (net (code "235") (name "unconnected-(LCD1-DB1-Pad8)") (class "Default")
      (node (ref "LCD1") (pin "8") (pinfunction "DB1_8") (pintype "unspecified+no_connect"))
    )
    (net (code "236") (name "unconnected-(LCD1-DB2-Pad9)") (class "Default")
      (node (ref "LCD1") (pin "9") (pinfunction "DB2_9") (pintype "unspecified+no_connect"))
    )
    (net (code "237") (name "unconnected-(LCD1-DB3-Pad10)") (class "Default")
      (node (ref "LCD1") (pin "10") (pinfunction "DB3_10") (pintype "unspecified+no_connect"))
    )
    (net (code "238") (name "unconnected-(R33-Pad2)") (class "Default")
      (node (ref "R33") (pin "2") (pinfunction "2_2") (pintype "input+no_connect"))
    )
    (net (code "239") (name "unconnected-(R34-Pad2)") (class "Default")
      (node (ref "R34") (pin "2") (pinfunction "2_2") (pintype "input+no_connect"))
    )
    (net (code "240") (name "unconnected-(R35-Pad2)") (class "Default")
      (node (ref "R35") (pin "2") (pinfunction "2_2") (pintype "input+no_connect"))
    )
    (net (code "241") (name "unconnected-(R36-Pad2)") (class "Default")
      (node (ref "R36") (pin "2") (pinfunction "2_2") (pintype "input+no_connect"))
    )
    (net (code "242") (name "unconnected-(R38-Pad2)") (class "Default")
      (node (ref "R38") (pin "2") (pinfunction "2_2") (pintype "input+no_connect"))
    )
    (net (code "243") (name "unconnected-(R39-Pad2)") (class "Default")
      (node (ref "R39") (pin "2") (pinfunction "2_2") (pintype "input+no_connect"))
    )
    (net (code "244") (name "unconnected-(R40-Pad2)") (class "Default")
      (node (ref "R40") (pin "2") (pinfunction "2_2") (pintype "input+no_connect"))
    )
    (net (code "245") (name "unconnected-(R41-Pad2)") (class "Default")
      (node (ref "R41") (pin "2") (pinfunction "2_2") (pintype "input+no_connect"))
    )
    (net (code "246") (name "unconnected-(R42-Pad2)") (class "Default")
      (node (ref "R42") (pin "2") (pinfunction "2_2") (pintype "input+no_connect"))
    )
    (net (code "247") (name "unconnected-(R43-Pad2)") (class "Default")
      (node (ref "R43") (pin "2") (pinfunction "2_2") (pintype "input+no_connect"))
    )
    (net (code "248") (name "unconnected-(R44-Pad2)") (class "Default")
      (node (ref "R44") (pin "2") (pinfunction "2_2") (pintype "input+no_connect"))
    )
    (net (code "249") (name "unconnected-(R51-Pad2)") (class "Default")
      (node (ref "R51") (pin "2") (pinfunction "2_2") (pintype "input+no_connect"))
    )
    (net (code "250") (name "unconnected-(R52-Pad2)") (class "Default")
      (node (ref "R52") (pin "2") (pinfunction "2_2") (pintype "input+no_connect"))
    )
    (net (code "251") (name "unconnected-(R53-Pad2)") (class "Default")
      (node (ref "R53") (pin "2") (pinfunction "2_2") (pintype "input+no_connect"))
    )
    (net (code "252") (name "unconnected-(R54-Pad2)") (class "Default")
      (node (ref "R54") (pin "2") (pinfunction "2_2") (pintype "input+no_connect"))
    )
    (net (code "253") (name "unconnected-(R55-Pad2)") (class "Default")
      (node (ref "R55") (pin "2") (pinfunction "2_2") (pintype "input+no_connect"))
    )
    (net (code "254") (name "unconnected-(SHIFT_REG1-Q7S-Pad9)") (class "Default")
      (node (ref "SHIFT_REG1") (pin "9") (pinfunction "Q7S_9") (pintype "unspecified+no_connect"))
    )
    (net (code "255") (name "unconnected-(U1-DB0-Pad7)") (class "Default")
      (node (ref "U1") (pin "7") (pinfunction "DB0_7") (pintype "unspecified+no_connect"))
    )
    (net (code "256") (name "unconnected-(U1-DB1-Pad8)") (class "Default")
      (node (ref "U1") (pin "8") (pinfunction "DB1_8") (pintype "unspecified+no_connect"))
    )
    (net (code "257") (name "unconnected-(U1-DB2-Pad9)") (class "Default")
      (node (ref "U1") (pin "9") (pinfunction "DB2_9") (pintype "unspecified+no_connect"))
    )
    (net (code "258") (name "unconnected-(U1-DB3-Pad10)") (class "Default")
      (node (ref "U1") (pin "10") (pinfunction "DB3_10") (pintype "unspecified+no_connect"))
    )
    (net (code "259") (name "unconnected-(U2-A-Pad7)") (class "Default")
      (node (ref "U2") (pin "7") (pinfunction "A_7") (pintype "unspecified+no_connect"))
    )
    (net (code "260") (name "unconnected-(U2-B-Pad6)") (class "Default")
      (node (ref "U2") (pin "6") (pinfunction "B_6") (pintype "unspecified+no_connect"))
    )
    (net (code "261") (name "unconnected-(U2-C-Pad4)") (class "Default")
      (node (ref "U2") (pin "4") (pinfunction "C_4") (pintype "unspecified+no_connect"))
    )
    (net (code "262") (name "unconnected-(U2-D-Pad2)") (class "Default")
      (node (ref "U2") (pin "2") (pinfunction "D_2") (pintype "unspecified+no_connect"))
    )
    (net (code "263") (name "unconnected-(U2-DP-Pad5)") (class "Default")
      (node (ref "U2") (pin "5") (pinfunction "DP_5") (pintype "unspecified+no_connect"))
    )
    (net (code "264") (name "unconnected-(U2-E-Pad1)") (class "Default")
      (node (ref "U2") (pin "1") (pinfunction "E_1") (pintype "unspecified+no_connect"))
    )
    (net (code "265") (name "unconnected-(U2-F-Pad9)") (class "Default")
      (node (ref "U2") (pin "9") (pinfunction "F_9") (pintype "unspecified+no_connect"))
    )
    (net (code "266") (name "unconnected-(U2-G-Pad10)") (class "Default")
      (node (ref "U2") (pin "10") (pinfunction "G_10") (pintype "unspecified+no_connect"))
    )
    (net (code "267") (name "unconnected-(U6-A-Pad7)") (class "Default")
      (node (ref "U6") (pin "7") (pinfunction "A_7") (pintype "unspecified+no_connect"))
    )
    (net (code "268") (name "unconnected-(U6-B-Pad6)") (class "Default")
      (node (ref "U6") (pin "6") (pinfunction "B_6") (pintype "unspecified+no_connect"))
    )
    (net (code "269") (name "unconnected-(U6-C-Pad4)") (class "Default")
      (node (ref "U6") (pin "4") (pinfunction "C_4") (pintype "unspecified+no_connect"))
    )
    (net (code "270") (name "unconnected-(U6-D-Pad2)") (class "Default")
      (node (ref "U6") (pin "2") (pinfunction "D_2") (pintype "unspecified+no_connect"))
    )
    (net (code "271") (name "unconnected-(U6-DP-Pad5)") (class "Default")
      (node (ref "U6") (pin "5") (pinfunction "DP_5") (pintype "unspecified+no_connect"))
    )
    (net (code "272") (name "unconnected-(U6-E-Pad1)") (class "Default")
      (node (ref "U6") (pin "1") (pinfunction "E_1") (pintype "unspecified+no_connect"))
    )
    (net (code "273") (name "unconnected-(U6-F-Pad9)") (class "Default")
      (node (ref "U6") (pin "9") (pinfunction "F_9") (pintype "unspecified+no_connect"))
    )
    (net (code "274") (name "unconnected-(U6-G-Pad10)") (class "Default")
      (node (ref "U6") (pin "10") (pinfunction "G_10") (pintype "unspecified+no_connect"))
    )
    (net (code "275") (name "unconnected-(U7-NC-Pad1)") (class "Default")
      (node (ref "U7") (pin "1") (pinfunction "NC_1") (pintype "unspecified+no_connect"))
    )
    (net (code "276") (name "unconnected-(U9-NC-Pad6)") (class "Default")
      (node (ref "U9") (pin "6") (pinfunction "NC_6") (pintype "unspecified+no_connect"))
    )
    (net (code "277") (name "unconnected-(U9-NC-Pad7)") (class "Default")
      (node (ref "U9") (pin "7") (pinfunction "NC_7") (pintype "unspecified+no_connect"))
    )
    (net (code "278") (name "unconnected-(USB_C1-SBU1-PadA8)") (class "Default")
      (node (ref "USB_C1") (pin "A8") (pinfunction "SBU1_A8") (pintype "unspecified"))
    )
    (net (code "279") (name "unconnected-(USB_C1-SBU2-PadB8)") (class "Default")
      (node (ref "USB_C1") (pin "B8") (pinfunction "SBU2_B8") (pintype "unspecified"))
    )
  )
)
